# cyclops_r3.net
KiCad netlist of a schematic drawn in EAGLE
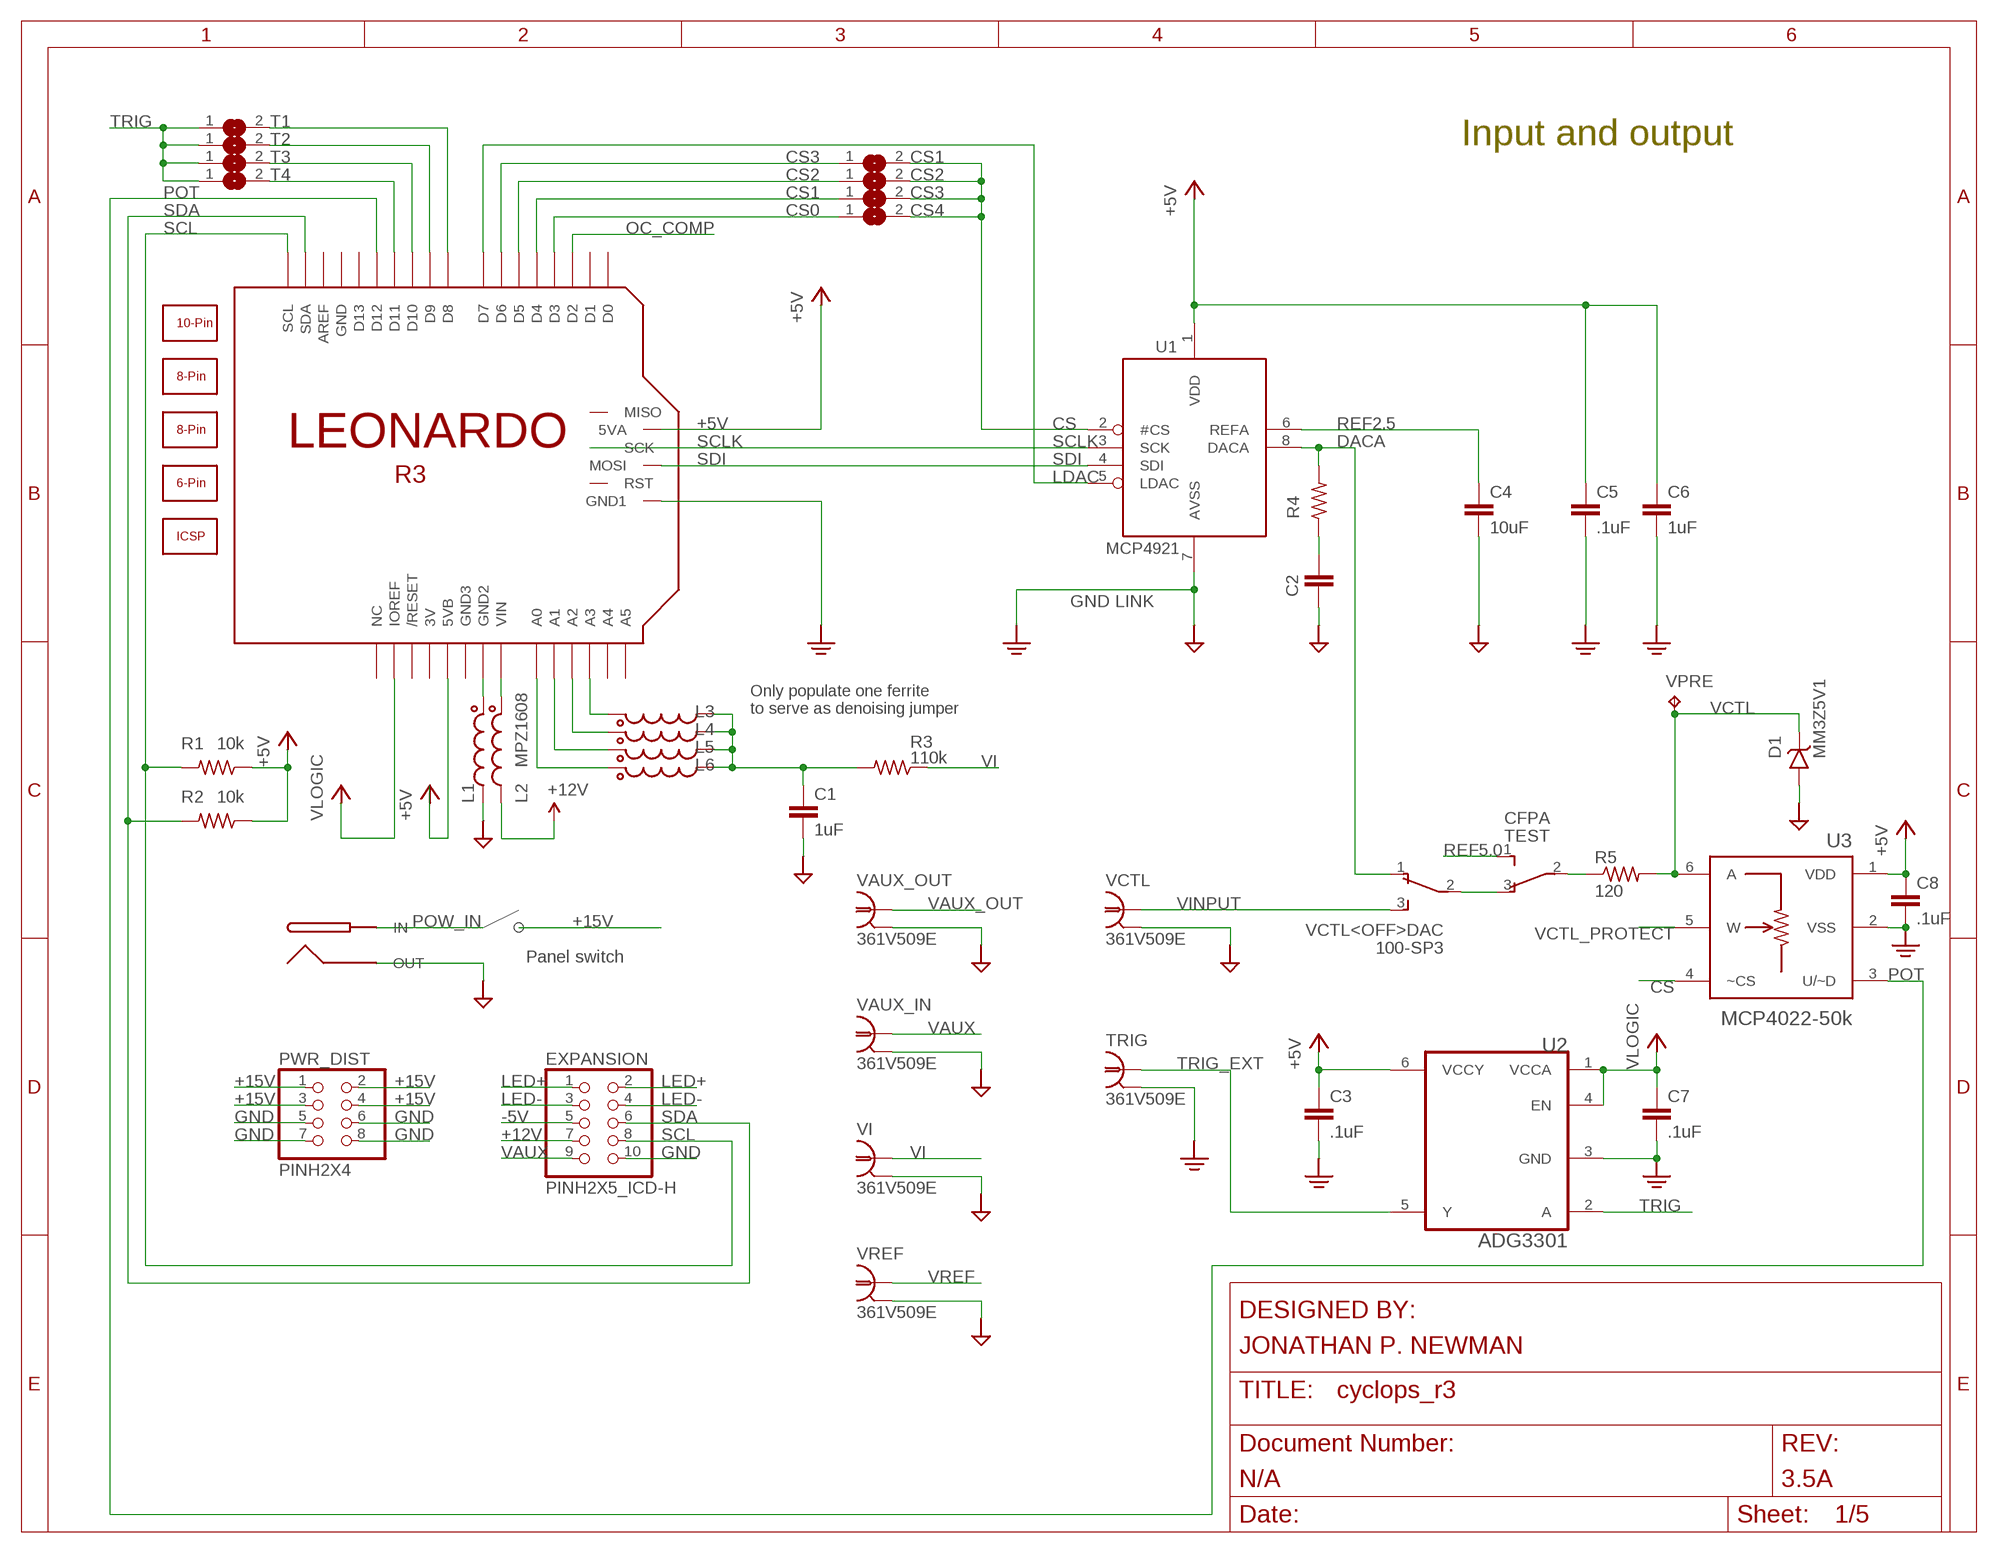
[diagram p0: schematic, sheet 1]
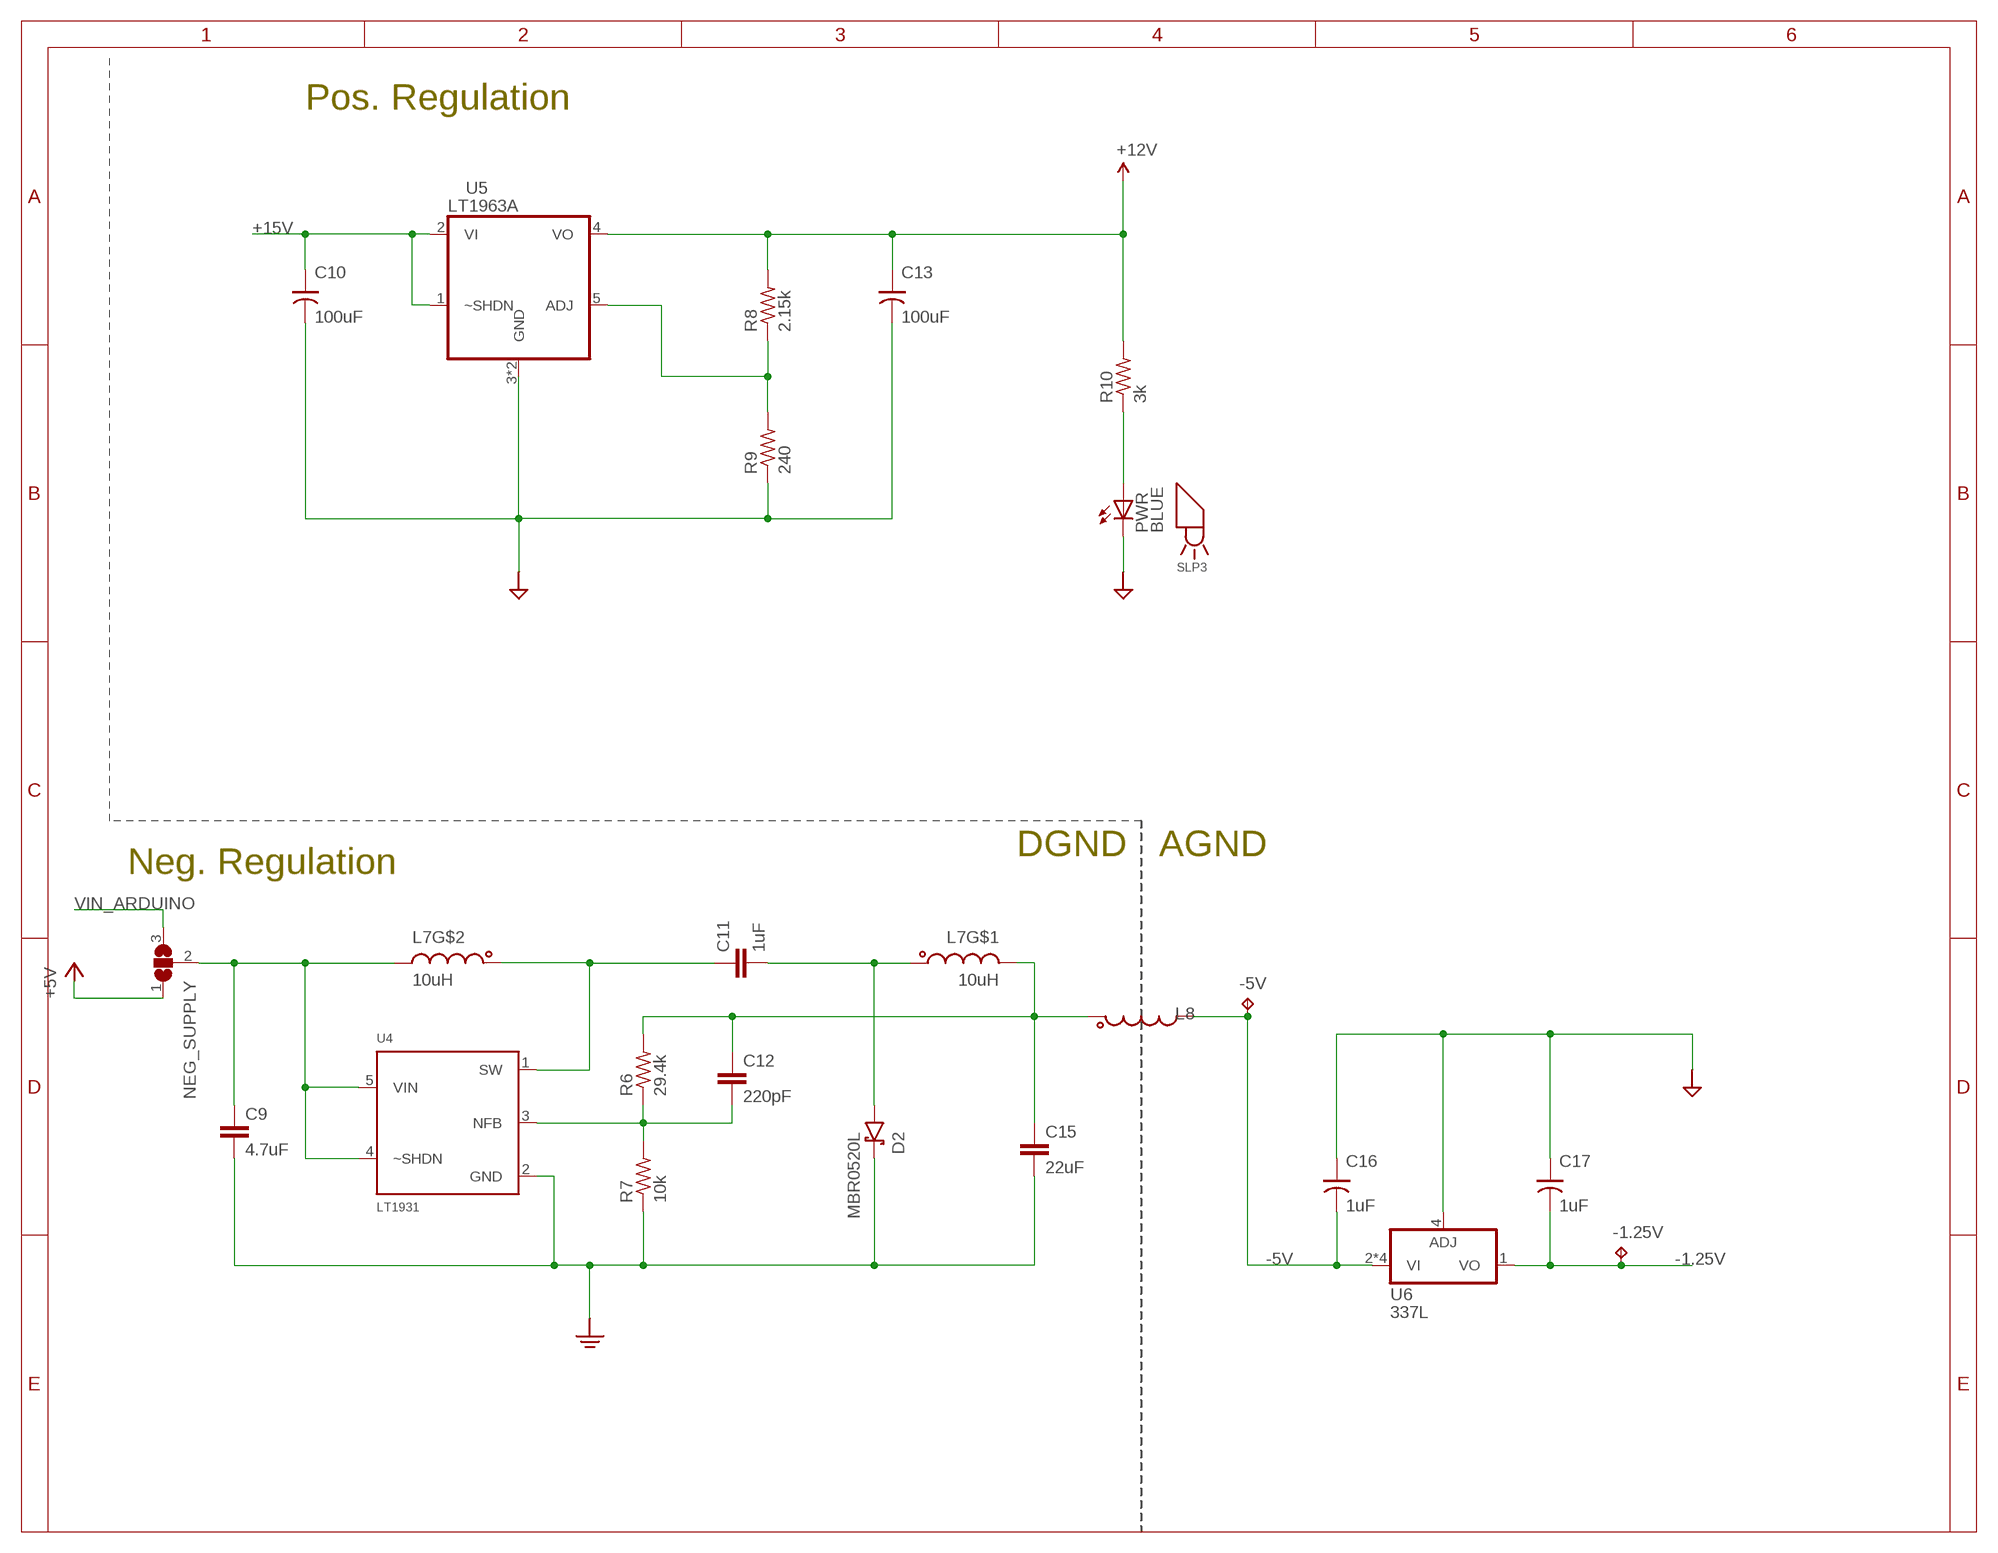
[diagram p1: schematic, sheet 2]
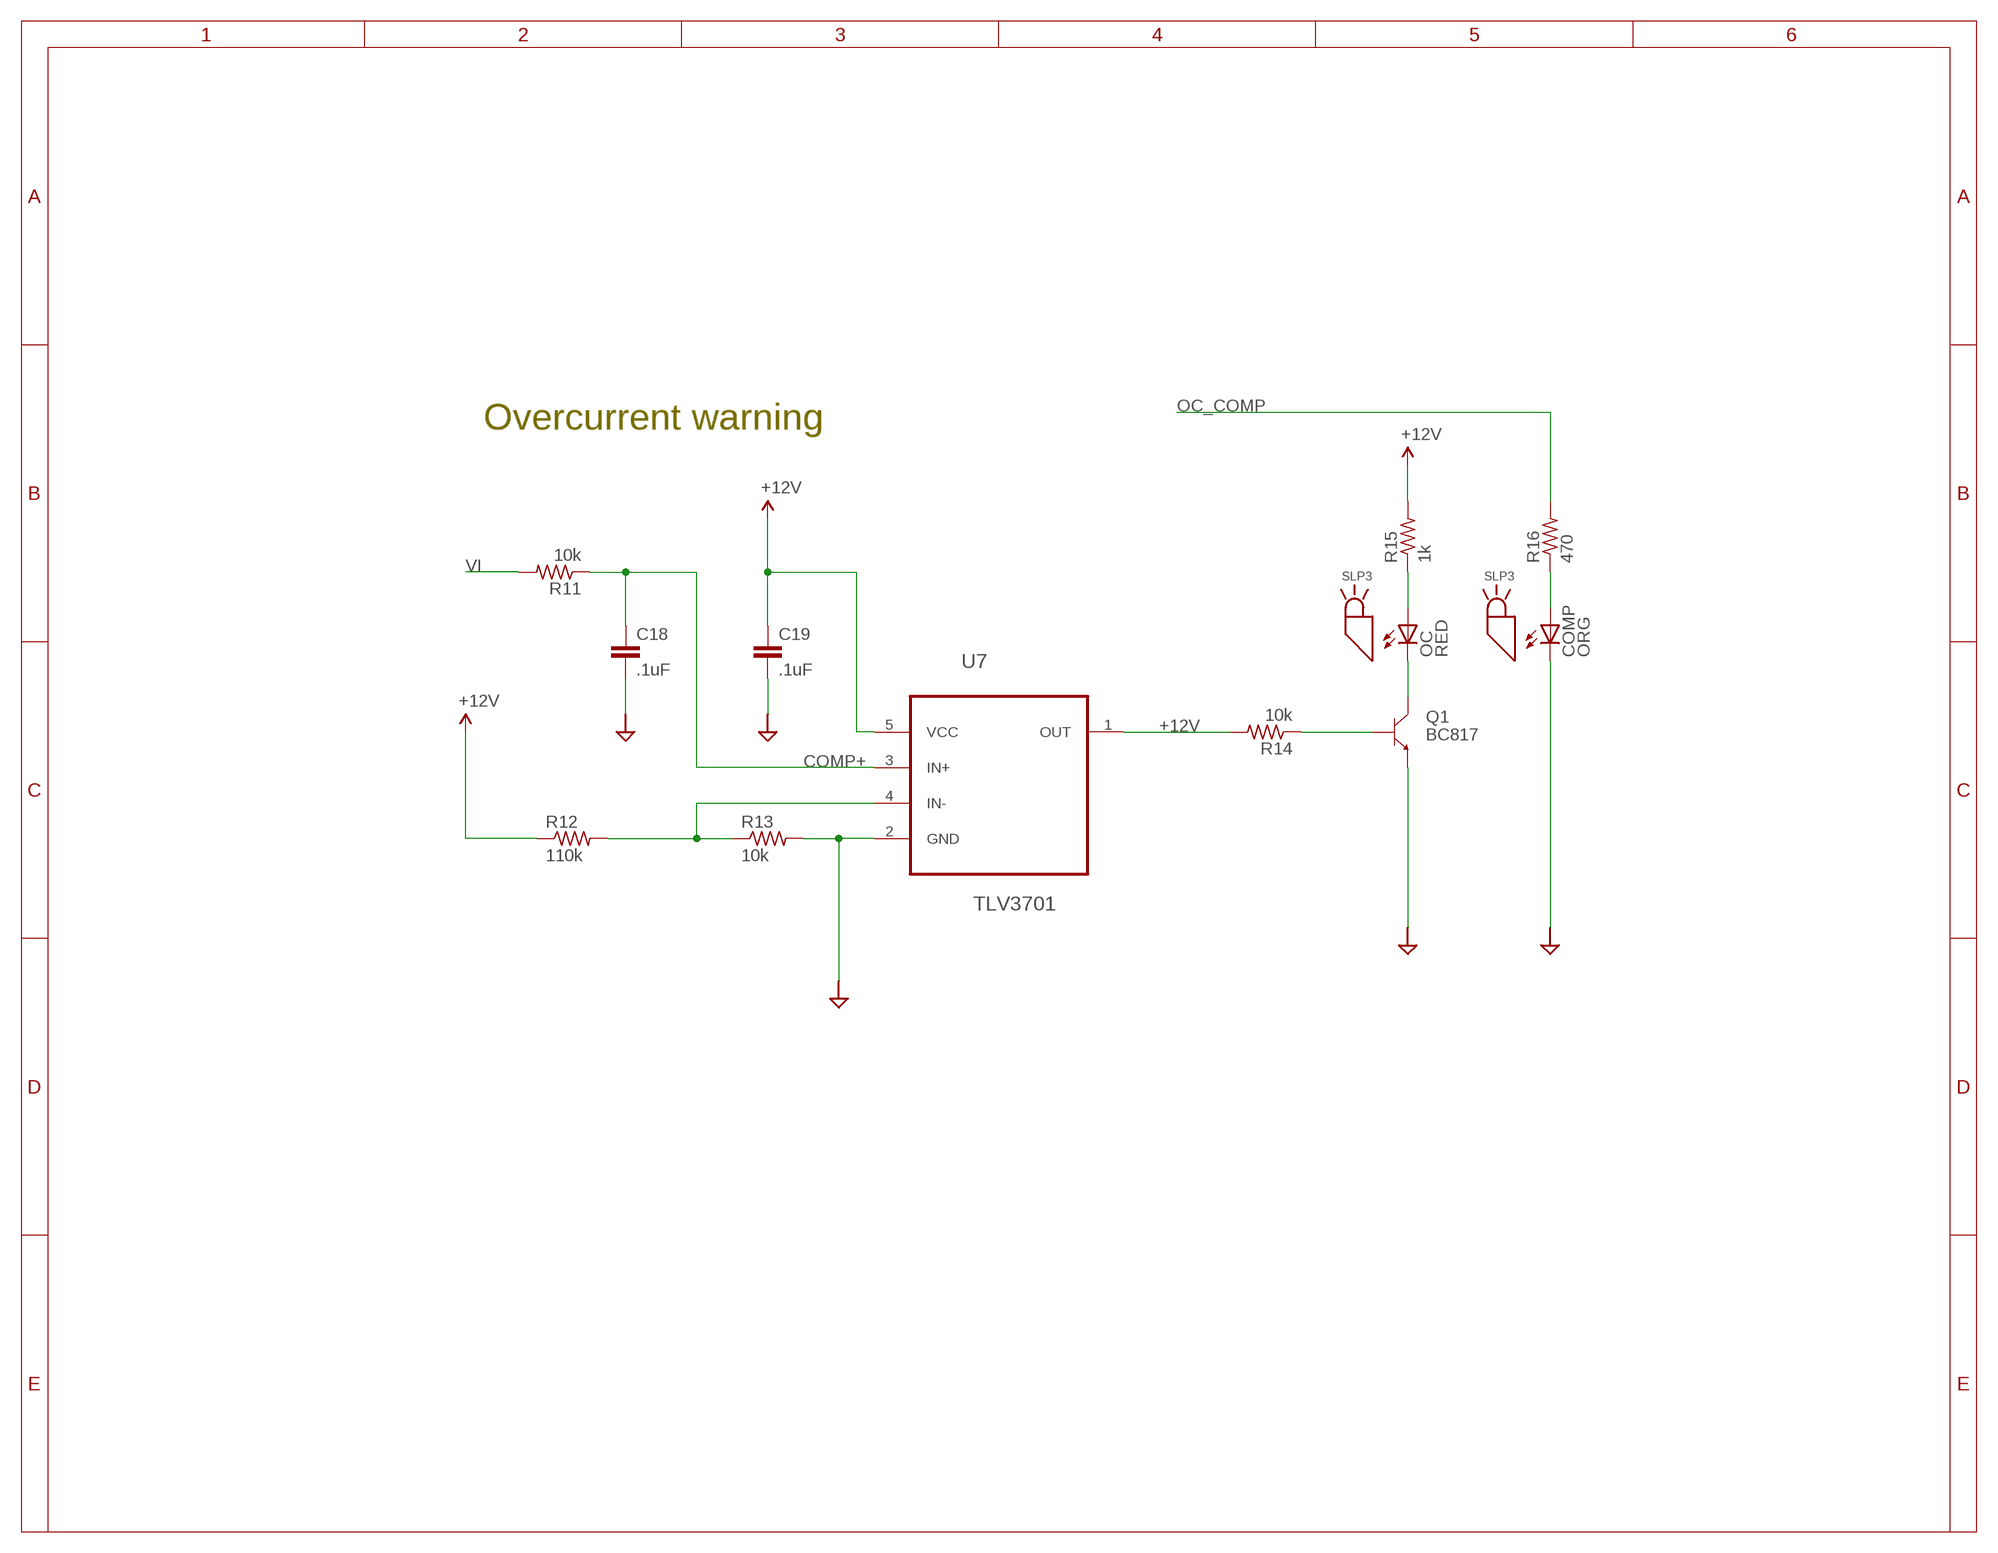
[diagram p2: schematic, sheet 3]
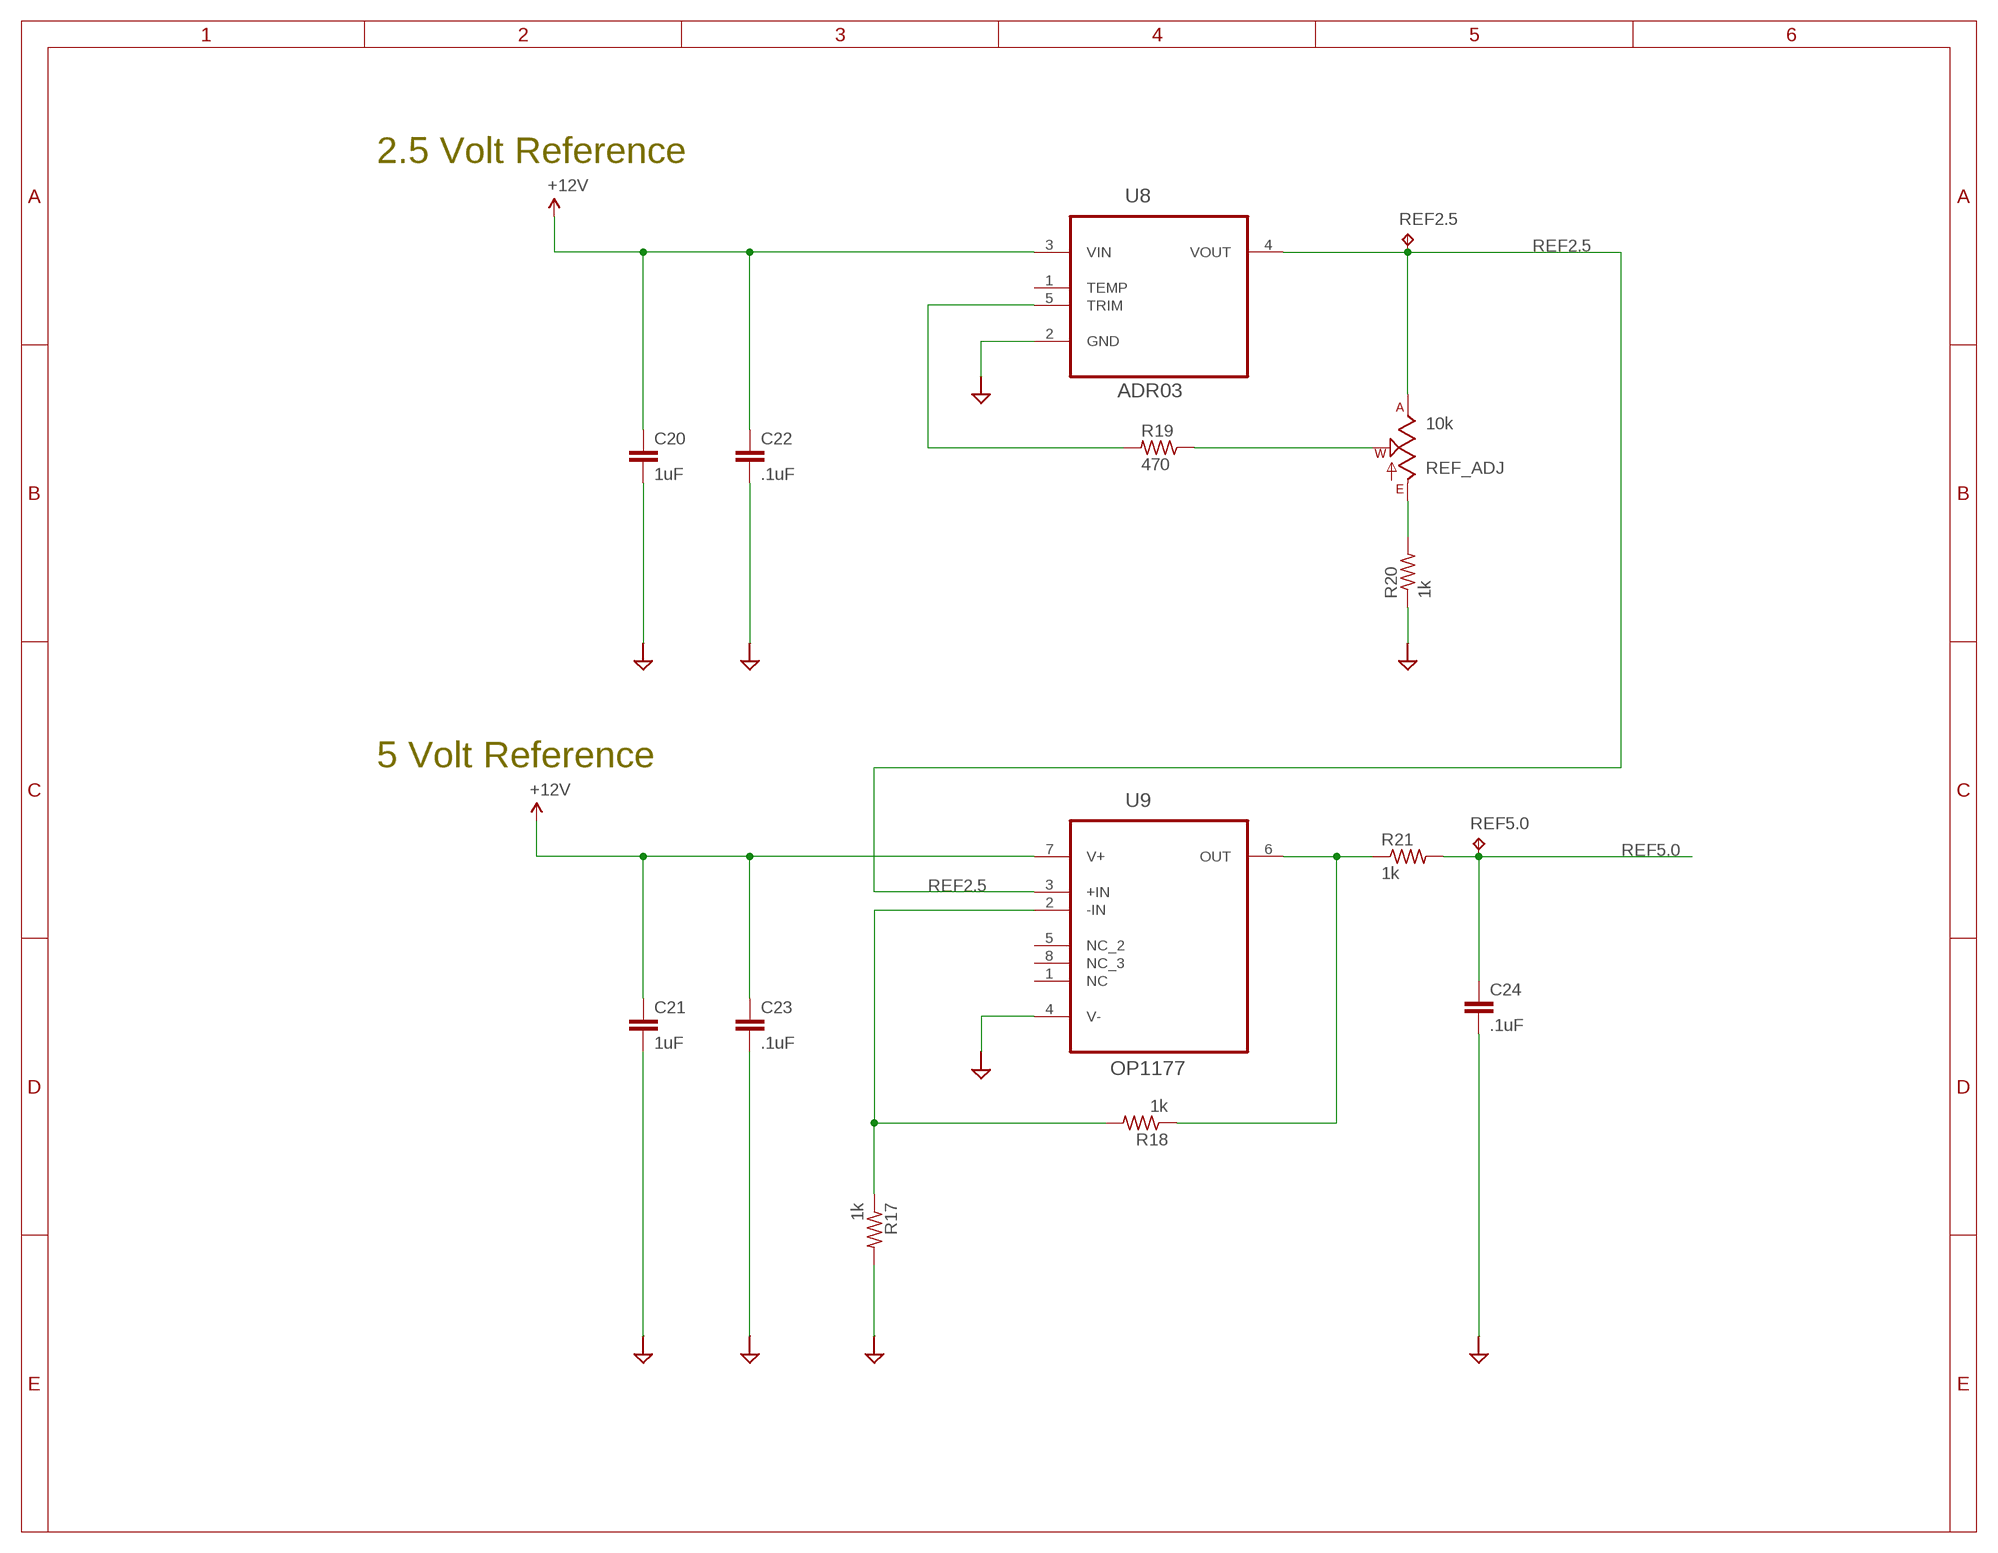
[diagram p3: schematic, sheet 4]
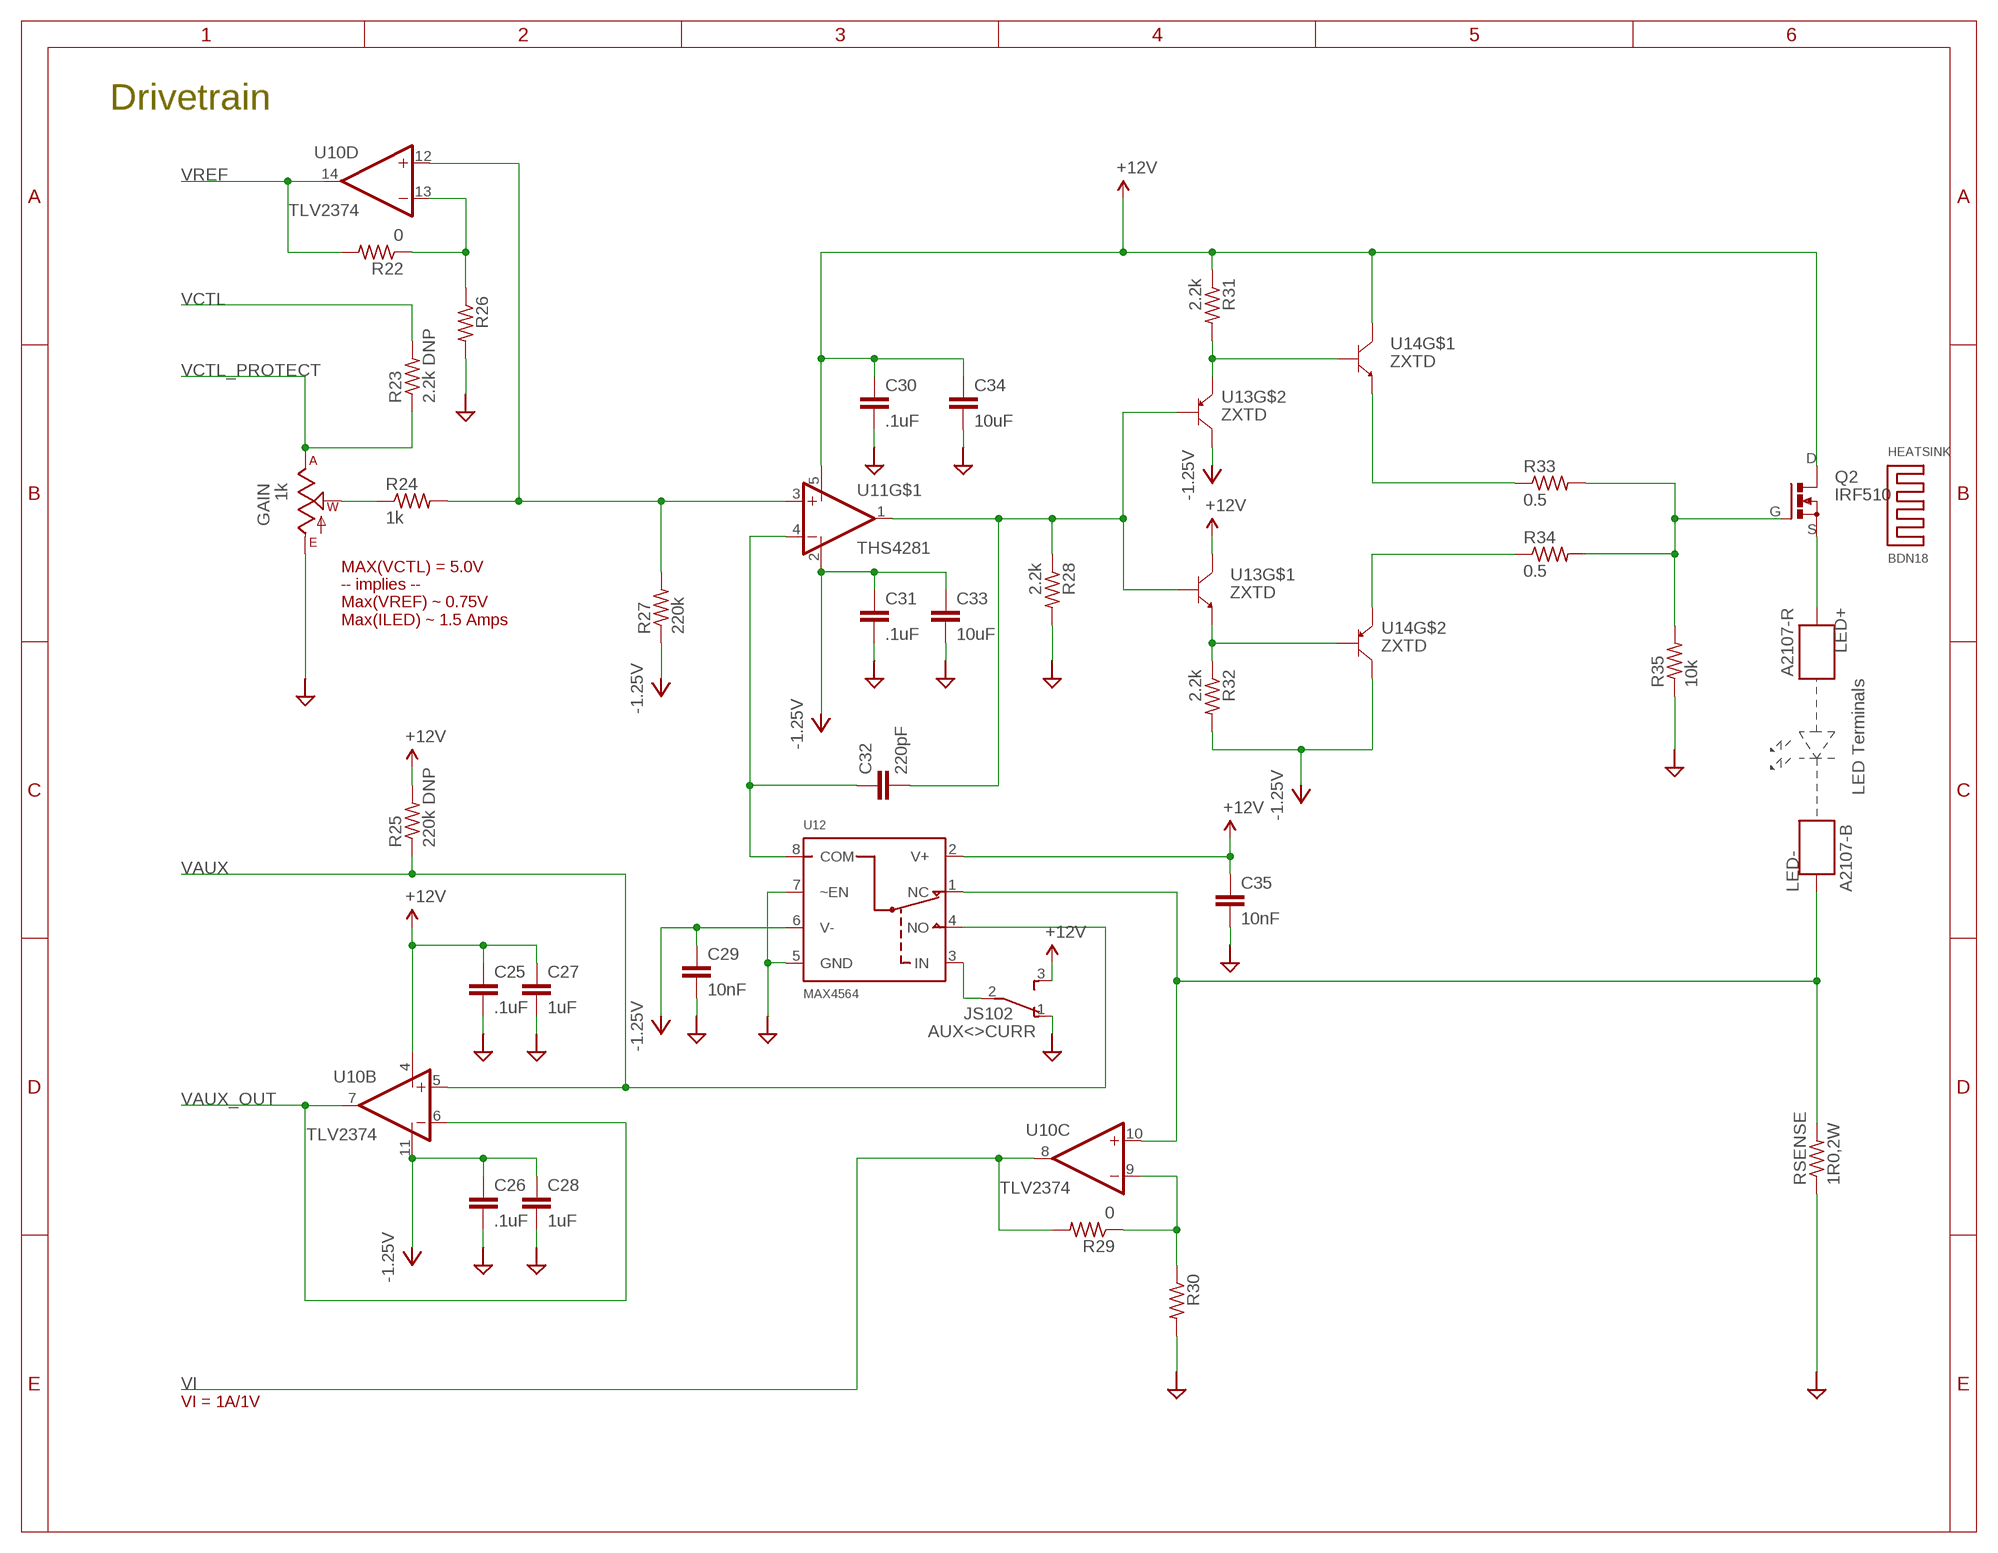
[diagram p4: schematic, sheet 5]

(export (version "E")
  (design (tool "Eeschema 10.0.6"))
  (components
    (comp (ref "C1")
      (value "1uF")
      (footprint "eagle-import:0805")
      (fields (field (name "PARTNO") "C2012X5R1Cxxxxxxx"))
      (libsource (lib "eagle-import") (part "C_0805"))
    )
    (comp (ref "C2")
      (value "C_0603")
      (footprint "eagle-import:0603")
      (libsource (lib "eagle-import") (part "C_0603"))
    )
    (comp (ref "C3")
      (value ".1uF")
      (footprint "eagle-import:0603")
      (libsource (lib "eagle-import") (part "C_0603"))
    )
    (comp (ref "C4")
      (value "10uF")
      (footprint "eagle-import:0805")
      (fields (field (name "PARTNO") "C2012X5R1Cxxxxxxx"))
      (libsource (lib "eagle-import") (part "C_0805"))
    )
    (comp (ref "C5")
      (value ".1uF")
      (footprint "eagle-import:0603")
      (libsource (lib "eagle-import") (part "C_0603"))
    )
    (comp (ref "C6")
      (value "1uF")
      (footprint "eagle-import:0805")
      (fields (field (name "PARTNO") "C2012X5R1Cxxxxxxx"))
      (libsource (lib "eagle-import") (part "C_0805"))
    )
    (comp (ref "C7")
      (value ".1uF")
      (footprint "eagle-import:0603")
      (libsource (lib "eagle-import") (part "C_0603"))
    )
    (comp (ref "C8")
      (value ".1uF")
      (footprint "eagle-import:0603")
      (libsource (lib "eagle-import") (part "C_0603"))
    )
    (comp (ref "CS1") (value "SJ") (footprint "eagle-import:SJ") (libsource (lib "eagle-import") (part "SJ")))
    (comp (ref "CS2") (value "SJ") (footprint "eagle-import:SJ") (libsource (lib "eagle-import") (part "SJ")))
    (comp (ref "CS3") (value "SJ") (footprint "eagle-import:SJ") (libsource (lib "eagle-import") (part "SJ")))
    (comp (ref "CS4") (value "SJ") (footprint "eagle-import:SJ") (libsource (lib "eagle-import") (part "SJ")))
    (comp (ref "D1")
      (value "MM3Z5V1")
      (footprint "eagle-import:SOD-323")
      (libsource (lib "eagle-import") (part "Z-DIODE_SOD-323"))
    )
    (comp (ref "EXPANSION")
      (value "PINH2X5_ICD-H")
      (footprint "eagle-import:2X05-IDC")
      (libsource (lib "eagle-import") (part "PINH2X5_ICD-H"))
    )
    (comp (ref "L1")
      (value "MPZ1608")
      (footprint "eagle-import:0603")
      (libsource (lib "eagle-import") (part "L_0603"))
    )
    (comp (ref "L2")
      (value "MPZ1608")
      (footprint "eagle-import:0603")
      (libsource (lib "eagle-import") (part "L_0603"))
    )
    (comp (ref "L3")
      (value "MPZ1608")
      (footprint "eagle-import:0603")
      (libsource (lib "eagle-import") (part "L_0603"))
    )
    (comp (ref "L4")
      (value "MPZ1608")
      (footprint "eagle-import:0603")
      (libsource (lib "eagle-import") (part "L_0603"))
    )
    (comp (ref "L5")
      (value "MPZ1608")
      (footprint "eagle-import:0603")
      (libsource (lib "eagle-import") (part "L_0603"))
    )
    (comp (ref "L6")
      (value "MPZ1608")
      (footprint "eagle-import:0603")
      (libsource (lib "eagle-import") (part "L_0603"))
    )
    (comp (ref "LEONARDO")
      (value "LEONARDO_R3_ICSP")
      (footprint "eagle-import:ARDUINOR3_PINS_NOHOLES")
      (libsource (lib "eagle-import") (part "LEONARDO_R3_ICSP"))
    )
    (comp (ref "POWER")
      (value "PJ-063BH")
      (footprint "eagle-import:PJ-063BH")
      (libsource (lib "eagle-import") (part "BARREL-JACK_PJ-063BH"))
    )
    (comp (ref "PWR_DIST")
      (value "PINH2X4")
      (footprint "eagle-import:2X04-BIG")
      (libsource (lib "eagle-import") (part "PINH2X4"))
    )
    (comp (ref "R1")
      (value "10k")
      (footprint "eagle-import:0603")
      (fields (field (name "MPN") "ERJ-3EKFxxxxV"))
      (libsource (lib "eagle-import") (part "R_0603"))
    )
    (comp (ref "R2")
      (value "10k")
      (footprint "eagle-import:0603")
      (fields (field (name "MPN") "ERJ-3EKFxxxxV"))
      (libsource (lib "eagle-import") (part "R_0603"))
    )
    (comp (ref "R3")
      (value "110k")
      (footprint "eagle-import:0603")
      (fields (field (name "MPN") "ERJ-3EKFxxxxV"))
      (libsource (lib "eagle-import") (part "R_0603"))
    )
    (comp (ref "R4")
      (value "R_0603")
      (footprint "eagle-import:0603")
      (fields (field (name "MPN") "ERJ-3EKFxxxxV"))
      (libsource (lib "eagle-import") (part "R_0603"))
    )
    (comp (ref "R5")
      (value "120")
      (footprint "eagle-import:0603")
      (fields (field (name "MPN") "ERJ-3EKFxxxxV"))
      (libsource (lib "eagle-import") (part "R_0603"))
    )
    (comp (ref "T1") (value "SJ") (footprint "eagle-import:SJ") (libsource (lib "eagle-import") (part "SJ")))
    (comp (ref "T2") (value "SJ") (footprint "eagle-import:SJ") (libsource (lib "eagle-import") (part "SJ")))
    (comp (ref "T3") (value "SJ") (footprint "eagle-import:SJ") (libsource (lib "eagle-import") (part "SJ")))
    (comp (ref "T4") (value "SJ") (footprint "eagle-import:SJ") (libsource (lib "eagle-import") (part "SJ")))
    (comp (ref "TEST")
      (value "CFPA")
      (footprint "eagle-import:CFPA")
      (libsource (lib "eagle-import") (part "SPDT_CFPA"))
    )
    (comp (ref "TRIG")
      (value "361V509E")
      (footprint "eagle-import:361V509E")
      (libsource (lib "eagle-import") (part "BNC_V-BITE"))
    )
    (comp (ref "U1")
      (value "MCP4921")
      (footprint "eagle-import:SO08")
      (libsource (lib "eagle-import") (part "MCP4921SOIC"))
    )
    (comp (ref "U2")
      (value "ADG3301")
      (footprint "eagle-import:SOT65P210X110-6N")
      (fields (field (name "MPN") "ADG3301BKSZ-REEL"))
      (libsource (lib "eagle-import") (part "ADG3301BKSZ-REEL"))
    )
    (comp (ref "U3")
      (value "MCP4022-50k")
      (footprint "eagle-import:SOT23-6")
      (libsource (lib "eagle-import") (part "MCP4022"))
    )
    (comp (ref "VAUX_IN")
      (value "361V509E")
      (footprint "eagle-import:361V509E")
      (libsource (lib "eagle-import") (part "BNC_V-BITE"))
    )
    (comp (ref "VAUX_OUT")
      (value "361V509E")
      (footprint "eagle-import:361V509E")
      (libsource (lib "eagle-import") (part "BNC_V-BITE"))
    )
    (comp (ref "VCTL")
      (value "361V509E")
      (footprint "eagle-import:361V509E")
      (libsource (lib "eagle-import") (part "BNC_V-BITE"))
    )
    (comp (ref "VCTL<OFF>DAC")
      (value "100-SP3")
      (footprint "eagle-import:2M1-SP1-T2-B4-M6RE")
      (libsource (lib "eagle-import") (part "SPDT_2M-WITHOFF"))
    )
    (comp (ref "VI")
      (value "361V509E")
      (footprint "eagle-import:361V509E")
      (libsource (lib "eagle-import") (part "BNC_V-BITE"))
    )
    (comp (ref "VPRE")
      (value "TPTP16R")
      (footprint "eagle-import:TP16R")
      (libsource (lib "eagle-import") (part "TPTP16R"))
    )
    (comp (ref "VREF")
      (value "361V509E")
      (footprint "eagle-import:361V509E")
      (libsource (lib "eagle-import") (part "BNC_V-BITE"))
    )
    (comp (ref "-1.25V")
      (value "TPTP16R")
      (footprint "eagle-import:TP16R")
      (libsource (lib "eagle-import") (part "TPTP16R"))
    )
    (comp (ref "-5V")
      (value "TPTP16R")
      (footprint "eagle-import:TP16R")
      (libsource (lib "eagle-import") (part "TPTP16R"))
    )
    (comp (ref "C9")
      (value "4.7uF")
      (footprint "eagle-import:1206")
      (libsource (lib "eagle-import") (part "C_1206"))
    )
    (comp (ref "C10")
      (value "100uF")
      (footprint "eagle-import:153CLV-0807")
      (libsource (lib "eagle-import") (part "C-POL_0807"))
    )
    (comp (ref "C11")
      (value "1uF")
      (footprint "eagle-import:1206")
      (libsource (lib "eagle-import") (part "C_1206"))
    )
    (comp (ref "C12")
      (value "220pF")
      (footprint "eagle-import:0603")
      (libsource (lib "eagle-import") (part "C_0603"))
    )
    (comp (ref "C13")
      (value "100uF")
      (footprint "eagle-import:153CLV-0807")
      (libsource (lib "eagle-import") (part "C-POL_0807"))
    )
    (comp (ref "C15")
      (value "22uF")
      (footprint "eagle-import:1210")
      (libsource (lib "eagle-import") (part "C_1210"))
    )
    (comp (ref "C16")
      (value "1uF")
      (footprint "eagle-import:1206-POL")
      (libsource (lib "eagle-import") (part "C-POL_1206"))
    )
    (comp (ref "C17")
      (value "1uF")
      (footprint "eagle-import:1206-POL")
      (libsource (lib "eagle-import") (part "C-POL_1206"))
    )
    (comp (ref "D2")
      (value "MBR0520L")
      (footprint "eagle-import:SOD123")
      (libsource (lib "eagle-import") (part "S-DIODESOD-123"))
    )
    (comp (ref "L7")
      (value "10uH")
      (footprint "eagle-import:CLS62")
      (libsource (lib "eagle-import") (part "2L_CLS62"))
    )
    (comp (ref "L8")
      (value "MPZ1608")
      (footprint "eagle-import:0603")
      (libsource (lib "eagle-import") (part "L_0603"))
    )
    (comp (ref "NEG_SUPPLY")
      (value "SJ2W")
      (footprint "eagle-import:SJ_2")
      (libsource (lib "eagle-import") (part "SJ2W"))
    )
    (comp (ref "PWR")
      (value "BLUE")
      (footprint "eagle-import:LED-0603")
      (libsource (lib "eagle-import") (part "LED_0603"))
    )
    (comp (ref "R6")
      (value "29.4k")
      (footprint "eagle-import:0603")
      (fields (field (name "MPN") "ERJ-3EKFxxxxV"))
      (libsource (lib "eagle-import") (part "R_0603"))
    )
    (comp (ref "R7")
      (value "10k")
      (footprint "eagle-import:0603")
      (fields (field (name "MPN") "ERJ-3EKFxxxxV"))
      (libsource (lib "eagle-import") (part "R_0603"))
    )
    (comp (ref "R8")
      (value "2.15k")
      (footprint "eagle-import:0603")
      (fields (field (name "MPN") "ERJ-3EKFxxxxV"))
      (libsource (lib "eagle-import") (part "R_0603"))
    )
    (comp (ref "R9")
      (value "240")
      (footprint "eagle-import:0603")
      (fields (field (name "MPN") "ERJ-3EKFxxxxV"))
      (libsource (lib "eagle-import") (part "R_0603"))
    )
    (comp (ref "R10")
      (value "3k")
      (footprint "eagle-import:0603")
      (fields (field (name "MPN") "ERJ-3EKFxxxxV"))
      (libsource (lib "eagle-import") (part "R_0603"))
    )
    (comp (ref "U4")
      (value "LT1931")
      (footprint "eagle-import:SOT95P310X175-5N")
      (libsource (lib "eagle-import") (part "LT1611"))
    )
    (comp (ref "U5")
      (value "LT1963A")
      (footprint "eagle-import:5-DDPAK")
      (libsource (lib "eagle-import") (part "LT1963_DDPAK"))
    )
    (comp (ref "U6")
      (value "337L")
      (footprint "eagle-import:SOIC127P600X175-8N")
      (libsource (lib "eagle-import") (part "337L"))
    )
    (comp (ref "X1")
      (value "SLP3")
      (footprint "eagle-import:SL3P-150-100-F")
      (libsource (lib "eagle-import") (part "LIGHT-PIPE_SL30-150-100-F"))
    )
    (comp (ref "C18")
      (value ".1uF")
      (footprint "eagle-import:0603")
      (libsource (lib "eagle-import") (part "C_0603"))
    )
    (comp (ref "C19")
      (value ".1uF")
      (footprint "eagle-import:0603")
      (libsource (lib "eagle-import") (part "C_0603"))
    )
    (comp (ref "COMP")
      (value "ORG")
      (footprint "eagle-import:LED-0603")
      (libsource (lib "eagle-import") (part "LED_0603"))
    )
    (comp (ref "OC")
      (value "RED")
      (footprint "eagle-import:LED-0603")
      (libsource (lib "eagle-import") (part "LED_0603"))
    )
    (comp (ref "Q1")
      (value "BC817")
      (footprint "eagle-import:SOT23-BEC")
      (libsource (lib "eagle-import") (part "BC817SMD-16"))
    )
    (comp (ref "R11")
      (value "10k")
      (footprint "eagle-import:0603")
      (fields (field (name "MPN") "ERJ-3EKFxxxxV"))
      (libsource (lib "eagle-import") (part "R_0603"))
    )
    (comp (ref "R12")
      (value "110k")
      (footprint "eagle-import:0603")
      (fields (field (name "MPN") "ERJ-3EKFxxxxV"))
      (libsource (lib "eagle-import") (part "R_0603"))
    )
    (comp (ref "R13")
      (value "10k")
      (footprint "eagle-import:0603")
      (fields (field (name "MPN") "ERJ-3EKFxxxxV"))
      (libsource (lib "eagle-import") (part "R_0603"))
    )
    (comp (ref "R14")
      (value "10k")
      (footprint "eagle-import:0603")
      (fields (field (name "MPN") "ERJ-3EKFxxxxV"))
      (libsource (lib "eagle-import") (part "R_0603"))
    )
    (comp (ref "R15")
      (value "1k")
      (footprint "eagle-import:0603")
      (fields (field (name "MPN") "ERJ-3EKFxxxxV"))
      (libsource (lib "eagle-import") (part "R_0603"))
    )
    (comp (ref "R16")
      (value "470")
      (footprint "eagle-import:0603")
      (fields (field (name "MPN") "ERJ-3EKFxxxxV"))
      (libsource (lib "eagle-import") (part "R_0603"))
    )
    (comp (ref "U7")
      (value "TLV3701")
      (footprint "eagle-import:SOT95P280X145-5N")
      (fields (field (name "MPN") "TLV3701CDBVT"))
      (libsource (lib "eagle-import") (part "TLV3701CDBVT"))
    )
    (comp (ref "X2")
      (value "SLP3")
      (footprint "eagle-import:SL3P-150-100-F")
      (libsource (lib "eagle-import") (part "LIGHT-PIPE_SL30-150-100-F"))
    )
    (comp (ref "X3")
      (value "SLP3")
      (footprint "eagle-import:SL3P-150-100-F")
      (libsource (lib "eagle-import") (part "LIGHT-PIPE_SL30-150-100-F"))
    )
    (comp (ref "C20")
      (value "1uF")
      (footprint "eagle-import:0805")
      (fields (field (name "PARTNO") "C2012X5R1Cxxxxxxx"))
      (libsource (lib "eagle-import") (part "C_0805"))
    )
    (comp (ref "C21")
      (value "1uF")
      (footprint "eagle-import:0805")
      (fields (field (name "PARTNO") "C2012X5R1Cxxxxxxx"))
      (libsource (lib "eagle-import") (part "C_0805"))
    )
    (comp (ref "C22")
      (value ".1uF")
      (footprint "eagle-import:0603")
      (libsource (lib "eagle-import") (part "C_0603"))
    )
    (comp (ref "C23")
      (value ".1uF")
      (footprint "eagle-import:0603")
      (libsource (lib "eagle-import") (part "C_0603"))
    )
    (comp (ref "C24")
      (value ".1uF")
      (footprint "eagle-import:0603")
      (libsource (lib "eagle-import") (part "C_0603"))
    )
    (comp (ref "R17")
      (value "1k")
      (footprint "eagle-import:0603")
      (fields (field (name "MPN") "ERJ-3EKFxxxxV"))
      (libsource (lib "eagle-import") (part "R_0603"))
    )
    (comp (ref "R18")
      (value "1k")
      (footprint "eagle-import:0603")
      (fields (field (name "MPN") "ERJ-3EKFxxxxV"))
      (libsource (lib "eagle-import") (part "R_0603"))
    )
    (comp (ref "R19")
      (value "470")
      (footprint "eagle-import:0603")
      (fields (field (name "MPN") "ERJ-3EKFxxxxV"))
      (libsource (lib "eagle-import") (part "R_0603"))
    )
    (comp (ref "R20")
      (value "1k")
      (footprint "eagle-import:0603")
      (fields (field (name "MPN") "ERJ-3EKFxxxxV"))
      (libsource (lib "eagle-import") (part "R_0603"))
    )
    (comp (ref "R21")
      (value "1k")
      (footprint "eagle-import:0603")
      (fields (field (name "MPN") "ERJ-3EKFxxxxV"))
      (libsource (lib "eagle-import") (part "R_0603"))
    )
    (comp (ref "REF2.5")
      (value "TPTP16R")
      (footprint "eagle-import:TP16R")
      (libsource (lib "eagle-import") (part "TPTP16R"))
    )
    (comp (ref "REF5.0")
      (value "TPTP16R")
      (footprint "eagle-import:TP16R")
      (libsource (lib "eagle-import") (part "TPTP16R"))
    )
    (comp (ref "REF_ADJ")
      (value "10k")
      (footprint "eagle-import:SM-42_43W")
      (libsource (lib "eagle-import") (part "TRIM_US-SM-42/43W"))
    )
    (comp (ref "U8")
      (value "ADR03")
      (footprint "eagle-import:SOT65P210X110-5N")
      (fields (field (name "MPN") "ADR03AKSZ-REEL7"))
      (libsource (lib "eagle-import") (part "ADR03AKSZ-REEL7"))
    )
    (comp (ref "U9")
      (value "OP1177")
      (footprint "eagle-import:SOP65P490X110-8N")
      (fields (field (name "MPN") "OP1177ARMZ"))
      (libsource (lib "eagle-import") (part "OP1177ARMZ"))
    )
    (comp (ref "AUX<>CURR")
      (value "JS102")
      (footprint "eagle-import:JS102011SAQN")
      (libsource (lib "eagle-import") (part "SPDT_JS"))
    )
    (comp (ref "C25")
      (value ".1uF")
      (footprint "eagle-import:0603")
      (libsource (lib "eagle-import") (part "C_0603"))
    )
    (comp (ref "C26")
      (value ".1uF")
      (footprint "eagle-import:0603")
      (libsource (lib "eagle-import") (part "C_0603"))
    )
    (comp (ref "C27")
      (value "1uF")
      (footprint "eagle-import:0805")
      (fields (field (name "PARTNO") "C2012X5R1Cxxxxxxx"))
      (libsource (lib "eagle-import") (part "C_0805"))
    )
    (comp (ref "C28")
      (value "1uF")
      (footprint "eagle-import:0805")
      (fields (field (name "PARTNO") "C2012X5R1Cxxxxxxx"))
      (libsource (lib "eagle-import") (part "C_0805"))
    )
    (comp (ref "C29")
      (value "10nF")
      (footprint "eagle-import:0603")
      (libsource (lib "eagle-import") (part "C_0603"))
    )
    (comp (ref "C30")
      (value ".1uF")
      (footprint "eagle-import:0603")
      (libsource (lib "eagle-import") (part "C_0603"))
    )
    (comp (ref "C31")
      (value ".1uF")
      (footprint "eagle-import:0603")
      (libsource (lib "eagle-import") (part "C_0603"))
    )
    (comp (ref "C32")
      (value "220pF")
      (footprint "eagle-import:0603")
      (libsource (lib "eagle-import") (part "C_0603"))
    )
    (comp (ref "C33")
      (value "10uF")
      (footprint "eagle-import:1206")
      (libsource (lib "eagle-import") (part "C_1206"))
    )
    (comp (ref "C34")
      (value "10uF")
      (footprint "eagle-import:1206")
      (libsource (lib "eagle-import") (part "C_1206"))
    )
    (comp (ref "C35")
      (value "10nF")
      (footprint "eagle-import:0603")
      (libsource (lib "eagle-import") (part "C_0603"))
    )
    (comp (ref "GAIN")
      (value "1k")
      (footprint "eagle-import:3310C-001")
      (libsource (lib "eagle-import") (part "POT_US_3310"))
    )
    (comp (ref "HEATSINK")
      (value "BDN18")
      (footprint "eagle-import:BDN18")
      (libsource (lib "eagle-import") (part "HEATSINK_BDN18"))
    )
    (comp (ref "LED+")
      (value "A2107-R")
      (footprint "eagle-import:A-2107")
      (libsource (lib "eagle-import") (part "BANANA_TO_BOARD_A2107"))
    )
    (comp (ref "LED-")
      (value "A2107-B")
      (footprint "eagle-import:A-2107")
      (libsource (lib "eagle-import") (part "BANANA_TO_BOARD_A2107"))
    )
    (comp (ref "Q2")
      (value "IRF510")
      (footprint "eagle-import:TO-262_01")
      (libsource (lib "eagle-import") (part "N-MOSFETTO-262"))
    )
    (comp (ref "R22")
      (value "0")
      (footprint "eagle-import:0603")
      (fields (field (name "MPN") "ERJ-3EKFxxxxV"))
      (libsource (lib "eagle-import") (part "R_0603"))
    )
    (comp (ref "R23")
      (value "2.2k")
      (footprint "eagle-import:0603")
      (fields (field (name "MPN") "ERJ-3EKFxxxxV"))
      (libsource (lib "eagle-import") (part "R_0603"))
    )
    (comp (ref "R24")
      (value "1k")
      (footprint "eagle-import:0603")
      (fields (field (name "MPN") "ERJ-3EKFxxxxV"))
      (libsource (lib "eagle-import") (part "R_0603"))
    )
    (comp (ref "R25")
      (value "220k")
      (footprint "eagle-import:0603")
      (fields (field (name "MPN") "ERJ-3EKFxxxxV"))
      (libsource (lib "eagle-import") (part "R_0603"))
    )
    (comp (ref "R26")
      (value "R_0603")
      (footprint "eagle-import:0603")
      (fields (field (name "MPN") "ERJ-3EKFxxxxV"))
      (libsource (lib "eagle-import") (part "R_0603"))
    )
    (comp (ref "R27")
      (value "220k")
      (footprint "eagle-import:0603")
      (fields (field (name "MPN") "ERJ-3EKFxxxxV"))
      (libsource (lib "eagle-import") (part "R_0603"))
    )
    (comp (ref "R28")
      (value "2.2k")
      (footprint "eagle-import:0603")
      (fields (field (name "MPN") "ERJ-3EKFxxxxV"))
      (libsource (lib "eagle-import") (part "R_0603"))
    )
    (comp (ref "R29")
      (value "0")
      (footprint "eagle-import:0603")
      (fields (field (name "MPN") "ERJ-3EKFxxxxV"))
      (libsource (lib "eagle-import") (part "R_0603"))
    )
    (comp (ref "R30")
      (value "R_0603")
      (footprint "eagle-import:0603")
      (fields (field (name "MPN") "ERJ-3EKFxxxxV"))
      (libsource (lib "eagle-import") (part "R_0603"))
    )
    (comp (ref "R31")
      (value "2.2k")
      (footprint "eagle-import:0603")
      (fields (field (name "MPN") "ERJ-3EKFxxxxV"))
      (libsource (lib "eagle-import") (part "R_0603"))
    )
    (comp (ref "R32")
      (value "2.2k")
      (footprint "eagle-import:0603")
      (fields (field (name "MPN") "ERJ-3EKFxxxxV"))
      (libsource (lib "eagle-import") (part "R_0603"))
    )
    (comp (ref "R33")
      (value "0.5")
      (footprint "eagle-import:0603")
      (fields (field (name "MPN") "ERJ-3EKFxxxxV"))
      (libsource (lib "eagle-import") (part "R_0603"))
    )
    (comp (ref "R34")
      (value "0.5")
      (footprint "eagle-import:0603")
      (fields (field (name "MPN") "ERJ-3EKFxxxxV"))
      (libsource (lib "eagle-import") (part "R_0603"))
    )
    (comp (ref "R35")
      (value "10k")
      (footprint "eagle-import:0603")
      (fields (field (name "MPN") "ERJ-3EKFxxxxV"))
      (libsource (lib "eagle-import") (part "R_0603"))
    )
    (comp (ref "RSENSE")
      (value "1R0,2W")
      (footprint "eagle-import:2512")
      (libsource (lib "eagle-import") (part "R_2512"))
    )
    (comp (ref "U10")
      (value "TLV2374")
      (footprint "eagle-import:SO14")
      (libsource (lib "eagle-import") (part "QUAD-OPAMP_14PIND"))
    )
    (comp (ref "U11")
      (value "THS4281")
      (footprint "eagle-import:SOT95P310X175-5N")
      (libsource (lib "eagle-import") (part "OPAMP_SOT-23"))
    )
    (comp (ref "U12")
      (value "MAX4564")
      (footprint "eagle-import:SOT65P300X175-N")
      (libsource (lib "eagle-import") (part "MAX4564"))
    )
    (comp (ref "U13")
      (value "ZXTD")
      (footprint "eagle-import:SOT23-6")
      (libsource (lib "eagle-import") (part "ZXTD4591E6"))
    )
    (comp (ref "U14")
      (value "ZXTD")
      (footprint "eagle-import:SOT23-6")
      (libsource (lib "eagle-import") (part "ZXTD4591E6"))
    )
  )
  (nets
    (net (code "1") (name "+5V") (class "Default")
      (node (ref "C3") (pin "1") (pinfunction "1_1") (pintype "passive"))
      (node (ref "C5") (pin "1") (pinfunction "1_1") (pintype "passive"))
      (node (ref "C6") (pin "1") (pinfunction "1_1") (pintype "passive"))
      (node (ref "C8") (pin "1") (pinfunction "1_1") (pintype "passive"))
      (node (ref "LEONARDO") (pin "5VA") (pinfunction "5VA_5VA") (pintype "passive"))
      (node (ref "LEONARDO") (pin "5VB") (pinfunction "5VB_5VB") (pintype "passive"))
      (node (ref "NEG_SUPPLY") (pin "1") (pinfunction "1_1") (pintype "passive"))
      (node (ref "R1") (pin "1") (pinfunction "1_1") (pintype "passive"))
      (node (ref "R2") (pin "1") (pinfunction "1_1") (pintype "passive"))
      (node (ref "U1") (pin "1") (pinfunction "VDD_1") (pintype "power_in"))
      (node (ref "U2") (pin "6") (pinfunction "VCCY_6") (pintype "power_in"))
      (node (ref "U3") (pin "1") (pinfunction "VDD_1") (pintype "bidirectional"))
    )
    (net (code "2") (name "+12V") (class "Default")
      (node (ref "AUX<>CURR") (pin "3") (pinfunction "3_3") (pintype "passive"))
      (node (ref "C13") (pin "+") (pinfunction "+_+") (pintype "passive"))
      (node (ref "C19") (pin "1") (pinfunction "1_1") (pintype "passive"))
      (node (ref "C20") (pin "1") (pinfunction "1_1") (pintype "passive"))
      (node (ref "C21") (pin "1") (pinfunction "1_1") (pintype "passive"))
      (node (ref "C22") (pin "1") (pinfunction "1_1") (pintype "passive"))
      (node (ref "C23") (pin "1") (pinfunction "1_1") (pintype "passive"))
      (node (ref "C25") (pin "1") (pinfunction "1_1") (pintype "passive"))
      (node (ref "C27") (pin "1") (pinfunction "1_1") (pintype "passive"))
      (node (ref "C30") (pin "1") (pinfunction "1_1") (pintype "passive"))
      (node (ref "C34") (pin "1") (pinfunction "1_1") (pintype "passive"))
      (node (ref "C35") (pin "1") (pinfunction "1_1") (pintype "passive"))
      (node (ref "EXPANSION") (pin "7") (pinfunction "7_7") (pintype "passive"))
      (node (ref "L2") (pin "2") (pinfunction "2_2") (pintype "passive"))
      (node (ref "Q2") (pin "D") (pinfunction "D_D") (pintype "bidirectional"))
      (node (ref "R10") (pin "2") (pinfunction "2_2") (pintype "passive"))
      (node (ref "R12") (pin "1") (pinfunction "1_1") (pintype "passive"))
      (node (ref "R15") (pin "2") (pinfunction "2_2") (pintype "passive"))
      (node (ref "R25") (pin "2") (pinfunction "2_2") (pintype "passive"))
      (node (ref "R31") (pin "1") (pinfunction "1_1") (pintype "passive"))
      (node (ref "R8") (pin "2") (pinfunction "2_2") (pintype "passive"))
      (node (ref "U10") (pin "4") (pinfunction "V+_4") (pintype "power_in"))
      (node (ref "U11") (pin "5") (pinfunction "V+_5") (pintype "power_in"))
      (node (ref "U12") (pin "2") (pinfunction "V+_2") (pintype "bidirectional"))
      (node (ref "U13") (pin "1") (pinfunction "C_1") (pintype "bidirectional"))
      (node (ref "U14") (pin "1") (pinfunction "C_1") (pintype "bidirectional"))
      (node (ref "U5") (pin "4") (pinfunction "VO_4") (pintype "power_in"))
      (node (ref "U7") (pin "5") (pinfunction "VCC_5") (pintype "power_in"))
      (node (ref "U8") (pin "3") (pinfunction "VIN_3") (pintype "power_in"))
      (node (ref "U9") (pin "7") (pinfunction "V+_7") (pintype "power_in"))
    )
    (net (code "3") (name "+15V") (class "Default")
      (node (ref "C10") (pin "+") (pinfunction "+_+") (pintype "passive"))
      (node (ref "PWR_DIST") (pin "1") (pinfunction "1_1") (pintype "passive"))
      (node (ref "PWR_DIST") (pin "2") (pinfunction "2_2") (pintype "passive"))
      (node (ref "PWR_DIST") (pin "3") (pinfunction "3_3") (pintype "passive"))
      (node (ref "PWR_DIST") (pin "4") (pinfunction "4_4") (pintype "passive"))
      (node (ref "U5") (pin "1") (pinfunction "~{SHDN}_1") (pintype "input"))
      (node (ref "U5") (pin "2") (pinfunction "VI_2") (pintype "power_in"))
    )
    (net (code "4") (name "-1.25V") (class "Default")
      (node (ref "-1.25V") (pin "TP") (pinfunction "TP_TP") (pintype "input"))
      (node (ref "C17") (pin "-") (pinfunction "-_-") (pintype "passive"))
      (node (ref "C26") (pin "1") (pinfunction "1_1") (pintype "passive"))
      (node (ref "C28") (pin "1") (pinfunction "1_1") (pintype "passive"))
      (node (ref "C29") (pin "1") (pinfunction "1_1") (pintype "passive"))
      (node (ref "C31") (pin "1") (pinfunction "1_1") (pintype "passive"))
      (node (ref "C33") (pin "1") (pinfunction "1_1") (pintype "passive"))
      (node (ref "R27") (pin "1") (pinfunction "1_1") (pintype "passive"))
      (node (ref "R32") (pin "2") (pinfunction "2_2") (pintype "passive"))
      (node (ref "U10") (pin "11") (pinfunction "V-_11") (pintype "power_in"))
      (node (ref "U11") (pin "2") (pinfunction "V-_2") (pintype "power_in"))
      (node (ref "U12") (pin "6") (pinfunction "V-_6") (pintype "power_in"))
      (node (ref "U13") (pin "3") (pinfunction "C_3") (pintype "bidirectional"))
      (node (ref "U14") (pin "3") (pinfunction "C_3") (pintype "bidirectional"))
      (node (ref "U6") (pin "1") (pinfunction "VO_1") (pintype "passive"))
    )
    (net (code "5") (name "-5V") (class "Default")
      (node (ref "-5V") (pin "TP") (pinfunction "TP_TP") (pintype "input"))
      (node (ref "C16") (pin "-") (pinfunction "-_-") (pintype "passive"))
      (node (ref "EXPANSION") (pin "5") (pinfunction "5_5") (pintype "passive"))
      (node (ref "L8") (pin "2") (pinfunction "2_2") (pintype "passive"))
      (node (ref "U6") (pin "2") (pinfunction "VI_2") (pintype "input"))
      (node (ref "U6") (pin "3") (pinfunction "VI_3") (pintype "input"))
      (node (ref "U6") (pin "6") (pinfunction "VI_6") (pintype "input"))
      (node (ref "U6") (pin "7") (pinfunction "VI_7") (pintype "input"))
    )
    (net (code "6") (name "COMP+") (class "Default")
      (node (ref "C18") (pin "1") (pinfunction "1_1") (pintype "passive"))
      (node (ref "R11") (pin "1") (pinfunction "1_1") (pintype "passive"))
      (node (ref "U7") (pin "3") (pinfunction "IN+_3") (pintype "input"))
    )
    (net (code "7") (name "CS") (class "Default")
      (node (ref "CS1") (pin "2") (pinfunction "2_2") (pintype "passive"))
      (node (ref "CS2") (pin "2") (pinfunction "2_2") (pintype "passive"))
      (node (ref "CS3") (pin "2") (pinfunction "2_2") (pintype "passive"))
      (node (ref "CS4") (pin "2") (pinfunction "2_2") (pintype "passive"))
      (node (ref "U1") (pin "2") (pinfunction "#CS_2") (pintype "input"))
      (node (ref "U3") (pin "4") (pinfunction "~{CS}_4") (pintype "bidirectional"))
    )
    (net (code "8") (name "CS0") (class "Default")
      (node (ref "CS4") (pin "1") (pinfunction "1_1") (pintype "passive"))
      (node (ref "LEONARDO") (pin "D3") (pinfunction "D3_D3") (pintype "bidirectional"))
    )
    (net (code "9") (name "CS1") (class "Default")
      (node (ref "CS3") (pin "1") (pinfunction "1_1") (pintype "passive"))
      (node (ref "LEONARDO") (pin "D4") (pinfunction "D4_D4") (pintype "bidirectional"))
    )
    (net (code "10") (name "CS2") (class "Default")
      (node (ref "CS2") (pin "1") (pinfunction "1_1") (pintype "passive"))
      (node (ref "LEONARDO") (pin "D5") (pinfunction "D5_D5") (pintype "bidirectional"))
    )
    (net (code "11") (name "CS3") (class "Default")
      (node (ref "CS1") (pin "1") (pinfunction "1_1") (pintype "passive"))
      (node (ref "LEONARDO") (pin "D6") (pinfunction "D6_D6") (pintype "bidirectional"))
    )
    (net (code "12") (name "DACA") (class "Default")
      (node (ref "R4") (pin "2") (pinfunction "2_2") (pintype "passive"))
      (node (ref "U1") (pin "8") (pinfunction "DACA_8") (pintype "output"))
      (node (ref "VCTL<OFF>DAC") (pin "1") (pinfunction "1_1") (pintype "passive"))
    )
    (net (code "13") (name "GND") (class "Default")
      (node (ref "AUX<>CURR") (pin "1") (pinfunction "1_1") (pintype "passive"))
      (node (ref "C1") (pin "2") (pinfunction "2_2") (pintype "passive"))
      (node (ref "C10") (pin "-") (pinfunction "-_-") (pintype "passive"))
      (node (ref "C13") (pin "-") (pinfunction "-_-") (pintype "passive"))
      (node (ref "C15") (pin "2") (pinfunction "2_2") (pintype "passive"))
      (node (ref "C16") (pin "+") (pinfunction "+_+") (pintype "passive"))
      (node (ref "C17") (pin "+") (pinfunction "+_+") (pintype "passive"))
      (node (ref "C18") (pin "2") (pinfunction "2_2") (pintype "passive"))
      (node (ref "C19") (pin "2") (pinfunction "2_2") (pintype "passive"))
      (node (ref "C2") (pin "2") (pinfunction "2_2") (pintype "passive"))
      (node (ref "C20") (pin "2") (pinfunction "2_2") (pintype "passive"))
      (node (ref "C21") (pin "2") (pinfunction "2_2") (pintype "passive"))
      (node (ref "C22") (pin "2") (pinfunction "2_2") (pintype "passive"))
      (node (ref "C23") (pin "2") (pinfunction "2_2") (pintype "passive"))
      (node (ref "C24") (pin "2") (pinfunction "2_2") (pintype "passive"))
      (node (ref "C25") (pin "2") (pinfunction "2_2") (pintype "passive"))
      (node (ref "C26") (pin "2") (pinfunction "2_2") (pintype "passive"))
      (node (ref "C27") (pin "2") (pinfunction "2_2") (pintype "passive"))
      (node (ref "C28") (pin "2") (pinfunction "2_2") (pintype "passive"))
      (node (ref "C29") (pin "2") (pinfunction "2_2") (pintype "passive"))
      (node (ref "C3") (pin "2") (pinfunction "2_2") (pintype "passive"))
      (node (ref "C30") (pin "2") (pinfunction "2_2") (pintype "passive"))
      (node (ref "C31") (pin "2") (pinfunction "2_2") (pintype "passive"))
      (node (ref "C33") (pin "2") (pinfunction "2_2") (pintype "passive"))
      (node (ref "C34") (pin "2") (pinfunction "2_2") (pintype "passive"))
      (node (ref "C35") (pin "2") (pinfunction "2_2") (pintype "passive"))
      (node (ref "C4") (pin "2") (pinfunction "2_2") (pintype "passive"))
      (node (ref "C5") (pin "2") (pinfunction "2_2") (pintype "passive"))
      (node (ref "C6") (pin "2") (pinfunction "2_2") (pintype "passive"))
      (node (ref "C7") (pin "2") (pinfunction "2_2") (pintype "passive"))
      (node (ref "C8") (pin "2") (pinfunction "2_2") (pintype "passive"))
      (node (ref "C9") (pin "2") (pinfunction "2_2") (pintype "passive"))
      (node (ref "COMP") (pin "C") (pinfunction "C_C") (pintype "passive"))
      (node (ref "D1") (pin "A") (pinfunction "A_A") (pintype "passive"))
      (node (ref "D2") (pin "C") (pinfunction "C_C") (pintype "passive"))
      (node (ref "EXPANSION") (pin "10") (pinfunction "10_10") (pintype "passive"))
      (node (ref "GAIN") (pin "1") (pinfunction "E_1") (pintype "passive"))
      (node (ref "L1") (pin "2") (pinfunction "2_2") (pintype "passive"))
      (node (ref "LEONARDO") (pin "GND1") (pinfunction "GND1_GND1") (pintype "passive"))
      (node (ref "POWER") (pin "2") (pinfunction "OUT_2") (pintype "bidirectional"))
      (node (ref "PWR") (pin "C") (pinfunction "C_C") (pintype "passive"))
      (node (ref "PWR_DIST") (pin "5") (pinfunction "5_5") (pintype "passive"))
      (node (ref "PWR_DIST") (pin "6") (pinfunction "6_6") (pintype "passive"))
      (node (ref "PWR_DIST") (pin "7") (pinfunction "7_7") (pintype "passive"))
      (node (ref "PWR_DIST") (pin "8") (pinfunction "8_8") (pintype "passive"))
      (node (ref "Q1") (pin "E") (pinfunction "E_E") (pintype "bidirectional"))
      (node (ref "R13") (pin "2") (pinfunction "2_2") (pintype "passive"))
      (node (ref "R17") (pin "2") (pinfunction "2_2") (pintype "passive"))
      (node (ref "R20") (pin "1") (pinfunction "1_1") (pintype "passive"))
      (node (ref "R26") (pin "2") (pinfunction "2_2") (pintype "passive"))
      (node (ref "R28") (pin "2") (pinfunction "2_2") (pintype "passive"))
      (node (ref "R30") (pin "2") (pinfunction "2_2") (pintype "passive"))
      (node (ref "R35") (pin "1") (pinfunction "1_1") (pintype "passive"))
      (node (ref "R7") (pin "1") (pinfunction "1_1") (pintype "passive"))
      (node (ref "R9") (pin "1") (pinfunction "1_1") (pintype "passive"))
      (node (ref "RSENSE") (pin "1") (pinfunction "1_1") (pintype "passive"))
      (node (ref "TRIG") (pin "2") (pinfunction "2_2") (pintype "passive"))
      (node (ref "TRIG") (pin "3") (pinfunction "2_3") (pintype "passive"))
      (node (ref "U1") (pin "7") (pinfunction "AVSS_7") (pintype "power_in"))
      (node (ref "U12") (pin "5") (pinfunction "GND_5") (pintype "power_in"))
      (node (ref "U12") (pin "7") (pinfunction "~{EN}_7") (pintype "bidirectional"))
      (node (ref "U2") (pin "3") (pinfunction "GND_3") (pintype "passive"))
      (node (ref "U3") (pin "2") (pinfunction "VSS_2") (pintype "bidirectional"))
      (node (ref "U4") (pin "2") (pinfunction "GND_2") (pintype "power_in"))
      (node (ref "U5") (pin "3") (pinfunction "GND_3") (pintype "power_in"))
      (node (ref "U5") (pin "TAB") (pinfunction "GND_TAB") (pintype "power_in"))
      (node (ref "U6") (pin "4") (pinfunction "ADJ_4") (pintype "input"))
      (node (ref "U7") (pin "2") (pinfunction "GND_2") (pintype "passive"))
      (node (ref "U8") (pin "2") (pinfunction "GND_2") (pintype "passive"))
      (node (ref "U9") (pin "4") (pinfunction "V-_4") (pintype "power_in"))
      (node (ref "VAUX_IN") (pin "2") (pinfunction "2_2") (pintype "passive"))
      (node (ref "VAUX_IN") (pin "3") (pinfunction "2_3") (pintype "passive"))
      (node (ref "VAUX_OUT") (pin "2") (pinfunction "2_2") (pintype "passive"))
      (node (ref "VAUX_OUT") (pin "3") (pinfunction "2_3") (pintype "passive"))
      (node (ref "VCTL") (pin "2") (pinfunction "2_2") (pintype "passive"))
      (node (ref "VCTL") (pin "3") (pinfunction "2_3") (pintype "passive"))
      (node (ref "VI") (pin "2") (pinfunction "2_2") (pintype "passive"))
      (node (ref "VI") (pin "3") (pinfunction "2_3") (pintype "passive"))
      (node (ref "VREF") (pin "2") (pinfunction "2_2") (pintype "passive"))
      (node (ref "VREF") (pin "3") (pinfunction "2_3") (pintype "passive"))
    )
    (net (code "14") (name "LDAC") (class "Default")
      (node (ref "LEONARDO") (pin "D7") (pinfunction "D7_D7") (pintype "bidirectional"))
      (node (ref "U1") (pin "5") (pinfunction "LDAC_5") (pintype "input"))
    )
    (net (code "15") (name "LED+") (class "Default")
      (node (ref "EXPANSION") (pin "1") (pinfunction "1_1") (pintype "passive"))
      (node (ref "EXPANSION") (pin "2") (pinfunction "2_2") (pintype "passive"))
      (node (ref "LED+") (pin "1") (pinfunction "1_1") (pintype "bidirectional"))
      (node (ref "LED+") (pin "2") (pinfunction "1_2") (pintype "bidirectional"))
      (node (ref "Q2") (pin "S") (pinfunction "S_S") (pintype "bidirectional"))
    )
    (net (code "16") (name "LED-") (class "Default")
      (node (ref "EXPANSION") (pin "3") (pinfunction "3_3") (pintype "passive"))
      (node (ref "EXPANSION") (pin "4") (pinfunction "4_4") (pintype "passive"))
      (node (ref "LED-") (pin "1") (pinfunction "1_1") (pintype "bidirectional"))
      (node (ref "LED-") (pin "2") (pinfunction "1_2") (pintype "bidirectional"))
      (node (ref "RSENSE") (pin "2") (pinfunction "2_2") (pintype "passive"))
      (node (ref "U10") (pin "10") (pinfunction "+IN_10") (pintype "input"))
      (node (ref "U12") (pin "1") (pinfunction "NC_1") (pintype "bidirectional"))
    )
    (net (code "17") (name "Net-(C1-Pad1)") (class "Default")
      (node (ref "C1") (pin "1") (pinfunction "1_1") (pintype "passive"))
      (node (ref "L3") (pin "2") (pinfunction "2_2") (pintype "passive"))
      (node (ref "L4") (pin "2") (pinfunction "2_2") (pintype "passive"))
      (node (ref "L5") (pin "2") (pinfunction "2_2") (pintype "passive"))
      (node (ref "L6") (pin "2") (pinfunction "2_2") (pintype "passive"))
      (node (ref "R3") (pin "2") (pinfunction "2_2") (pintype "passive"))
    )
    (net (code "18") (name "Net-(C2-Pad1)") (class "Default")
      (node (ref "C2") (pin "1") (pinfunction "1_1") (pintype "passive"))
      (node (ref "R4") (pin "1") (pinfunction "1_1") (pintype "passive"))
    )
    (net (code "19") (name "Net-(C11-Pad2)") (class "Default")
      (node (ref "C11") (pin "2") (pinfunction "2_2") (pintype "passive"))
      (node (ref "D2") (pin "A") (pinfunction "A_A") (pintype "passive"))
      (node (ref "L7") (pin "1") (pinfunction "1_1") (pintype "passive"))
    )
    (net (code "20") (name "Net-(COMP-PadA)") (class "Default")
      (node (ref "COMP") (pin "A") (pinfunction "A_A") (pintype "passive"))
      (node (ref "R16") (pin "1") (pinfunction "1_1") (pintype "passive"))
    )
    (net (code "21") (name "Net-(GAIN-W)") (class "Default")
      (node (ref "GAIN") (pin "2") (pinfunction "W_2") (pintype "passive"))
      (node (ref "R24") (pin "1") (pinfunction "1_1") (pintype "passive"))
    )
    (net (code "22") (name "Net-(L1-Pad1)") (class "Default")
      (node (ref "L1") (pin "1") (pinfunction "1_1") (pintype "passive"))
      (node (ref "LEONARDO") (pin "GND2") (pinfunction "GND2_GND2") (pintype "passive"))
    )
    (net (code "23") (name "Net-(L3-Pad1)") (class "Default")
      (node (ref "L3") (pin "1") (pinfunction "1_1") (pintype "passive"))
      (node (ref "LEONARDO") (pin "A3") (pinfunction "A3_A3") (pintype "bidirectional"))
    )
    (net (code "24") (name "Net-(L4-Pad1)") (class "Default")
      (node (ref "L4") (pin "1") (pinfunction "1_1") (pintype "passive"))
      (node (ref "LEONARDO") (pin "A2") (pinfunction "A2_A2") (pintype "bidirectional"))
    )
    (net (code "25") (name "Net-(L5-Pad1)") (class "Default")
      (node (ref "L5") (pin "1") (pinfunction "1_1") (pintype "passive"))
      (node (ref "LEONARDO") (pin "A1") (pinfunction "A1_A1") (pintype "bidirectional"))
    )
    (net (code "26") (name "Net-(L6-Pad1)") (class "Default")
      (node (ref "L6") (pin "1") (pinfunction "1_1") (pintype "passive"))
      (node (ref "LEONARDO") (pin "A0") (pinfunction "A0_A0") (pintype "bidirectional"))
    )
    (net (code "27") (name "Net-(L7A-2)") (class "Default")
      (node (ref "C12") (pin "1") (pinfunction "1_1") (pintype "passive"))
      (node (ref "C15") (pin "1") (pinfunction "1_1") (pintype "passive"))
      (node (ref "L7") (pin "4") (pinfunction "2_4") (pintype "passive"))
      (node (ref "L8") (pin "1") (pinfunction "1_1") (pintype "passive"))
      (node (ref "R6") (pin "2") (pinfunction "2_2") (pintype "passive"))
    )
    (net (code "28") (name "Net-(L7B-1)") (class "Default")
      (node (ref "C11") (pin "1") (pinfunction "1_1") (pintype "passive"))
      (node (ref "L7") (pin "2") (pinfunction "1_2") (pintype "passive"))
      (node (ref "U4") (pin "1") (pinfunction "SW_1") (pintype "bidirectional"))
    )
    (net (code "29") (name "Net-(L7B-2)") (class "Default")
      (node (ref "C9") (pin "1") (pinfunction "1_1") (pintype "passive"))
      (node (ref "L7") (pin "3") (pinfunction "2_3") (pintype "passive"))
      (node (ref "NEG_SUPPLY") (pin "2") (pinfunction "2_2") (pintype "passive"))
      (node (ref "U4") (pin "4") (pinfunction "~{SHDN}_4") (pintype "bidirectional"))
      (node (ref "U4") (pin "5") (pinfunction "VIN_5") (pintype "power_in"))
    )
    (net (code "30") (name "Net-(LEONARDO-PadD8)") (class "Default")
      (node (ref "LEONARDO") (pin "D8") (pinfunction "D8_D8") (pintype "bidirectional"))
      (node (ref "T1") (pin "2") (pinfunction "2_2") (pintype "passive"))
    )
    (net (code "31") (name "Net-(LEONARDO-PadD9)") (class "Default")
      (node (ref "LEONARDO") (pin "D9") (pinfunction "D9_D9") (pintype "bidirectional"))
      (node (ref "T2") (pin "2") (pinfunction "2_2") (pintype "passive"))
    )
    (net (code "32") (name "Net-(LEONARDO-PadD10)") (class "Default")
      (node (ref "LEONARDO") (pin "D10") (pinfunction "D10_D10") (pintype "bidirectional"))
      (node (ref "T3") (pin "2") (pinfunction "2_2") (pintype "passive"))
    )
    (net (code "33") (name "Net-(LEONARDO-PadD11)") (class "Default")
      (node (ref "LEONARDO") (pin "D11") (pinfunction "D11_D11") (pintype "bidirectional"))
      (node (ref "T4") (pin "2") (pinfunction "2_2") (pintype "passive"))
    )
    (net (code "34") (name "Net-(OC-PadA)") (class "Default")
      (node (ref "OC") (pin "A") (pinfunction "A_A") (pintype "passive"))
      (node (ref "R15") (pin "1") (pinfunction "1_1") (pintype "passive"))
    )
    (net (code "35") (name "Net-(OC-PadC)") (class "Default")
      (node (ref "OC") (pin "C") (pinfunction "C_C") (pintype "passive"))
      (node (ref "Q1") (pin "C") (pinfunction "C_C") (pintype "bidirectional"))
    )
    (net (code "36") (name "Net-(PWR-PadA)") (class "Default")
      (node (ref "PWR") (pin "A") (pinfunction "A_A") (pintype "passive"))
      (node (ref "R10") (pin "1") (pinfunction "1_1") (pintype "passive"))
    )
    (net (code "37") (name "Net-(Q1-PadB)") (class "Default")
      (node (ref "Q1") (pin "B") (pinfunction "B_B") (pintype "input"))
      (node (ref "R14") (pin "1") (pinfunction "1_1") (pintype "passive"))
    )
    (net (code "38") (name "Net-(Q2-PadG)") (class "Default")
      (node (ref "Q2") (pin "G") (pinfunction "G_G") (pintype "bidirectional"))
      (node (ref "R33") (pin "2") (pinfunction "2_2") (pintype "passive"))
      (node (ref "R34") (pin "2") (pinfunction "2_2") (pintype "passive"))
      (node (ref "R35") (pin "2") (pinfunction "2_2") (pintype "passive"))
    )
    (net (code "39") (name "Net-(R5-Pad1)") (class "Default")
      (node (ref "R5") (pin "1") (pinfunction "1_1") (pintype "passive"))
      (node (ref "TEST") (pin "2") (pinfunction "2_2") (pintype "passive"))
    )
    (net (code "40") (name "Net-(REF_ADJ-E)") (class "Default")
      (node (ref "R20") (pin "2") (pinfunction "2_2") (pintype "passive"))
      (node (ref "REF_ADJ") (pin "3") (pinfunction "E_3") (pintype "passive"))
    )
    (net (code "41") (name "Net-(REF_ADJ-W)") (class "Default")
      (node (ref "R19") (pin "1") (pinfunction "1_1") (pintype "passive"))
      (node (ref "REF_ADJ") (pin "2") (pinfunction "W_2") (pintype "passive"))
    )
    (net (code "42") (name "Net-(TEST-1)") (class "Default")
      (node (ref "TEST") (pin "3") (pinfunction "1_3") (pintype "passive"))
      (node (ref "VCTL<OFF>DAC") (pin "2") (pinfunction "2_2") (pintype "passive"))
    )
    (net (code "43") (name "Net-(U4-NFB)") (class "Default")
      (node (ref "C12") (pin "2") (pinfunction "2_2") (pintype "passive"))
      (node (ref "R6") (pin "1") (pinfunction "1_1") (pintype "passive"))
      (node (ref "R7") (pin "2") (pinfunction "2_2") (pintype "passive"))
      (node (ref "U4") (pin "3") (pinfunction "NFB_3") (pintype "bidirectional"))
    )
    (net (code "44") (name "Net-(U5-ADJ)") (class "Default")
      (node (ref "R8") (pin "1") (pinfunction "1_1") (pintype "passive"))
      (node (ref "R9") (pin "2") (pinfunction "2_2") (pintype "passive"))
      (node (ref "U5") (pin "5") (pinfunction "ADJ_5") (pintype "input"))
    )
    (net (code "45") (name "Net-(U7-IN-)") (class "Default")
      (node (ref "R12") (pin "2") (pinfunction "2_2") (pintype "passive"))
      (node (ref "R13") (pin "1") (pinfunction "1_1") (pintype "passive"))
      (node (ref "U7") (pin "4") (pinfunction "IN-_4") (pintype "input"))
    )
    (net (code "46") (name "Net-(U7-OUT)") (class "Default")
      (node (ref "R14") (pin "2") (pinfunction "2_2") (pintype "passive"))
      (node (ref "U7") (pin "1") (pinfunction "OUT_1") (pintype "output"))
    )
    (net (code "47") (name "Net-(U8-TRIM)") (class "Default")
      (node (ref "R19") (pin "2") (pinfunction "2_2") (pintype "passive"))
      (node (ref "U8") (pin "5") (pinfunction "TRIM_5") (pintype "passive"))
    )
    (net (code "48") (name "Net-(U9--IN)") (class "Default")
      (node (ref "R17") (pin "1") (pinfunction "1_1") (pintype "passive"))
      (node (ref "R18") (pin "2") (pinfunction "2_2") (pintype "passive"))
      (node (ref "U9") (pin "2") (pinfunction "-IN_2") (pintype "input"))
    )
    (net (code "49") (name "Net-(U9-OUT)") (class "Default")
      (node (ref "R18") (pin "1") (pinfunction "1_1") (pintype "passive"))
      (node (ref "R21") (pin "1") (pinfunction "1_1") (pintype "passive"))
      (node (ref "U9") (pin "6") (pinfunction "OUT_6") (pintype "output"))
    )
    (net (code "50") (name "Net-(U10C--IN)") (class "Default")
      (node (ref "R29") (pin "1") (pinfunction "1_1") (pintype "passive"))
      (node (ref "R30") (pin "1") (pinfunction "1_1") (pintype "passive"))
      (node (ref "U10") (pin "9") (pinfunction "-IN_9") (pintype "input"))
    )
    (net (code "51") (name "Net-(U10D-+IN)") (class "Default")
      (node (ref "R24") (pin "2") (pinfunction "2_2") (pintype "passive"))
      (node (ref "R27") (pin "2") (pinfunction "2_2") (pintype "passive"))
      (node (ref "U10") (pin "12") (pinfunction "+IN_12") (pintype "input"))
      (node (ref "U11") (pin "3") (pinfunction "+IN_3") (pintype "input"))
    )
    (net (code "52") (name "Net-(U10D--IN)") (class "Default")
      (node (ref "R22") (pin "1") (pinfunction "1_1") (pintype "passive"))
      (node (ref "R26") (pin "1") (pinfunction "1_1") (pintype "passive"))
      (node (ref "U10") (pin "13") (pinfunction "-IN_13") (pintype "input"))
    )
    (net (code "53") (name "Net-(U11A--IN)") (class "Default")
      (node (ref "C32") (pin "1") (pinfunction "1_1") (pintype "passive"))
      (node (ref "U11") (pin "4") (pinfunction "-IN_4") (pintype "input"))
      (node (ref "U12") (pin "8") (pinfunction "COM_8") (pintype "power_in"))
    )
    (net (code "54") (name "Net-(U11A-OUT)") (class "Default")
      (node (ref "C32") (pin "2") (pinfunction "2_2") (pintype "passive"))
      (node (ref "R28") (pin "1") (pinfunction "1_1") (pintype "passive"))
      (node (ref "U11") (pin "1") (pinfunction "OUT_1") (pintype "output"))
      (node (ref "U13") (pin "2") (pinfunction "B_2") (pintype "input"))
      (node (ref "U13") (pin "5") (pinfunction "B_5") (pintype "input"))
    )
    (net (code "55") (name "Net-(U12-IN)") (class "Default")
      (node (ref "AUX<>CURR") (pin "2") (pinfunction "2_2") (pintype "passive"))
      (node (ref "U12") (pin "3") (pinfunction "IN_3") (pintype "bidirectional"))
    )
    (net (code "56") (name "Net-(U13A-E)") (class "Default")
      (node (ref "R32") (pin "1") (pinfunction "1_1") (pintype "passive"))
      (node (ref "U13") (pin "6") (pinfunction "E_6") (pintype "bidirectional"))
      (node (ref "U14") (pin "5") (pinfunction "B_5") (pintype "input"))
    )
    (net (code "57") (name "Net-(U13B-E)") (class "Default")
      (node (ref "R31") (pin "2") (pinfunction "2_2") (pintype "passive"))
      (node (ref "U13") (pin "4") (pinfunction "E_4") (pintype "bidirectional"))
      (node (ref "U14") (pin "2") (pinfunction "B_2") (pintype "input"))
    )
    (net (code "58") (name "Net-(U14A-E)") (class "Default")
      (node (ref "R33") (pin "1") (pinfunction "1_1") (pintype "passive"))
      (node (ref "U14") (pin "6") (pinfunction "E_6") (pintype "bidirectional"))
    )
    (net (code "59") (name "Net-(U14B-E)") (class "Default")
      (node (ref "R34") (pin "1") (pinfunction "1_1") (pintype "passive"))
      (node (ref "U14") (pin "4") (pinfunction "E_4") (pintype "bidirectional"))
    )
    (net (code "60") (name "OC_COMP") (class "Default")
      (node (ref "LEONARDO") (pin "D2") (pinfunction "D2_D2") (pintype "bidirectional"))
      (node (ref "R16") (pin "2") (pinfunction "2_2") (pintype "passive"))
    )
    (net (code "61") (name "POT") (class "Default")
      (node (ref "LEONARDO") (pin "D12") (pinfunction "D12_D12") (pintype "bidirectional"))
      (node (ref "U3") (pin "3") (pinfunction "U/~{D}_3") (pintype "bidirectional"))
    )
    (net (code "62") (name "POW_IN") (class "Default")
      (node (ref "POWER") (pin "1") (pinfunction "IN_1") (pintype "bidirectional"))
    )
    (net (code "63") (name "REF2.5") (class "Default")
      (node (ref "C4") (pin "1") (pinfunction "1_1") (pintype "passive"))
      (node (ref "REF2.5") (pin "TP") (pinfunction "TP_TP") (pintype "input"))
      (node (ref "REF_ADJ") (pin "1") (pinfunction "A_1") (pintype "passive"))
      (node (ref "U1") (pin "6") (pinfunction "REFA_6") (pintype "input"))
      (node (ref "U8") (pin "4") (pinfunction "VOUT_4") (pintype "output"))
      (node (ref "U9") (pin "3") (pinfunction "+IN_3") (pintype "input"))
    )
    (net (code "64") (name "REF5.0") (class "Default")
      (node (ref "C24") (pin "1") (pinfunction "1_1") (pintype "passive"))
      (node (ref "R21") (pin "2") (pinfunction "2_2") (pintype "passive"))
      (node (ref "REF5.0") (pin "TP") (pinfunction "TP_TP") (pintype "input"))
      (node (ref "TEST") (pin "1") (pinfunction "3_1") (pintype "passive"))
    )
    (net (code "65") (name "SCL") (class "Default")
      (node (ref "EXPANSION") (pin "8") (pinfunction "8_8") (pintype "passive"))
      (node (ref "LEONARDO") (pin "SCL") (pinfunction "SCL_SCL") (pintype "bidirectional"))
      (node (ref "R1") (pin "2") (pinfunction "2_2") (pintype "passive"))
    )
    (net (code "66") (name "SCLK") (class "Default")
      (node (ref "LEONARDO") (pin "SCK") (pinfunction "SCK_SCK") (pintype "passive"))
      (node (ref "U1") (pin "3") (pinfunction "SCK_3") (pintype "input"))
    )
    (net (code "67") (name "SDA") (class "Default")
      (node (ref "EXPANSION") (pin "6") (pinfunction "6_6") (pintype "passive"))
      (node (ref "LEONARDO") (pin "SDA") (pinfunction "SDA_SDA") (pintype "bidirectional"))
      (node (ref "R2") (pin "2") (pinfunction "2_2") (pintype "passive"))
    )
    (net (code "68") (name "SDI") (class "Default")
      (node (ref "LEONARDO") (pin "MOSI") (pinfunction "MOSI_MOSI") (pintype "passive"))
      (node (ref "U1") (pin "4") (pinfunction "SDI_4") (pintype "input"))
    )
    (net (code "69") (name "TRIG") (class "Default")
      (node (ref "T1") (pin "1") (pinfunction "1_1") (pintype "passive"))
      (node (ref "T2") (pin "1") (pinfunction "1_1") (pintype "passive"))
      (node (ref "T3") (pin "1") (pinfunction "1_1") (pintype "passive"))
      (node (ref "T4") (pin "1") (pinfunction "1_1") (pintype "passive"))
      (node (ref "U2") (pin "2") (pinfunction "A_2") (pintype "bidirectional"))
    )
    (net (code "70") (name "TRIG_EXT") (class "Default")
      (node (ref "TRIG") (pin "1") (pinfunction "1_1") (pintype "passive"))
      (node (ref "U2") (pin "5") (pinfunction "Y_5") (pintype "bidirectional"))
    )
    (net (code "71") (name "VAUX") (class "Default")
      (node (ref "EXPANSION") (pin "9") (pinfunction "9_9") (pintype "passive"))
      (node (ref "R25") (pin "1") (pinfunction "1_1") (pintype "passive"))
      (node (ref "U10") (pin "5") (pinfunction "+IN_5") (pintype "input"))
      (node (ref "U12") (pin "4") (pinfunction "NO_4") (pintype "bidirectional"))
      (node (ref "VAUX_IN") (pin "1") (pinfunction "1_1") (pintype "passive"))
    )
    (net (code "72") (name "VAUX_OUT") (class "Default")
      (node (ref "U10") (pin "6") (pinfunction "-IN_6") (pintype "input"))
      (node (ref "U10") (pin "7") (pinfunction "OUT_7") (pintype "output"))
      (node (ref "VAUX_OUT") (pin "1") (pinfunction "1_1") (pintype "passive"))
    )
    (net (code "73") (name "VCTL") (class "Default")
      (node (ref "D1") (pin "C") (pinfunction "C_C") (pintype "passive"))
      (node (ref "R23") (pin "2") (pinfunction "2_2") (pintype "passive"))
      (node (ref "R5") (pin "2") (pinfunction "2_2") (pintype "passive"))
      (node (ref "U3") (pin "6") (pinfunction "A_6") (pintype "bidirectional"))
      (node (ref "VPRE") (pin "TP") (pinfunction "TP_TP") (pintype "input"))
    )
    (net (code "74") (name "VCTL_PROTECT") (class "Default")
      (node (ref "GAIN") (pin "3") (pinfunction "A_3") (pintype "passive"))
      (node (ref "R23") (pin "1") (pinfunction "1_1") (pintype "passive"))
      (node (ref "U3") (pin "5") (pinfunction "W_5") (pintype "bidirectional"))
    )
    (net (code "75") (name "VI") (class "Default")
      (node (ref "R11") (pin "2") (pinfunction "2_2") (pintype "passive"))
      (node (ref "R29") (pin "2") (pinfunction "2_2") (pintype "passive"))
      (node (ref "R3") (pin "1") (pinfunction "1_1") (pintype "passive"))
      (node (ref "U10") (pin "8") (pinfunction "OUT_8") (pintype "output"))
      (node (ref "VI") (pin "1") (pinfunction "1_1") (pintype "passive"))
    )
    (net (code "76") (name "VINPUT") (class "Default")
      (node (ref "VCTL") (pin "1") (pinfunction "1_1") (pintype "passive"))
      (node (ref "VCTL<OFF>DAC") (pin "3") (pinfunction "3_3") (pintype "passive"))
    )
    (net (code "77") (name "VIN_ARDUINO") (class "Default")
      (node (ref "L2") (pin "1") (pinfunction "1_1") (pintype "passive"))
      (node (ref "LEONARDO") (pin "VIN") (pinfunction "VIN_VIN") (pintype "power_in"))
      (node (ref "NEG_SUPPLY") (pin "3") (pinfunction "3_3") (pintype "passive"))
    )
    (net (code "78") (name "VLOGIC") (class "Default")
      (node (ref "C7") (pin "1") (pinfunction "1_1") (pintype "passive"))
      (node (ref "LEONARDO") (pin "IOREF") (pinfunction "IOREF_IOREF") (pintype "output"))
      (node (ref "U2") (pin "1") (pinfunction "VCCA_1") (pintype "power_in"))
      (node (ref "U2") (pin "4") (pinfunction "EN_4") (pintype "input"))
    )
    (net (code "79") (name "VREF") (class "Default")
      (node (ref "R22") (pin "2") (pinfunction "2_2") (pintype "passive"))
      (node (ref "U10") (pin "14") (pinfunction "OUT_14") (pintype "output"))
      (node (ref "VREF") (pin "1") (pinfunction "1_1") (pintype "passive"))
    )
    (net (code "80") (name "unconnected-(LEONARDO-NC-PadRESERVED)") (class "Default")
      (node (ref "LEONARDO") (pin "RESERVED") (pinfunction "NC_RESERVED") (pintype "no_connect"))
    )
    (net (code "81") (name "unconnected-(LEONARDO-Pad3V)") (class "Default")
      (node (ref "LEONARDO") (pin "3V") (pinfunction "3V_3V") (pintype "passive"))
    )
    (net (code "82") (name "unconnected-(LEONARDO-PadA4)") (class "Default")
      (node (ref "LEONARDO") (pin "A4") (pinfunction "A4_A4") (pintype "bidirectional"))
    )
    (net (code "83") (name "unconnected-(LEONARDO-PadA5)") (class "Default")
      (node (ref "LEONARDO") (pin "A5") (pinfunction "A5_A5") (pintype "bidirectional"))
    )
    (net (code "84") (name "unconnected-(LEONARDO-PadAREF)") (class "Default")
      (node (ref "LEONARDO") (pin "AREF") (pinfunction "AREF_AREF") (pintype "bidirectional"))
    )
    (net (code "85") (name "unconnected-(LEONARDO-PadD0)") (class "Default")
      (node (ref "LEONARDO") (pin "D0") (pinfunction "D0_D0") (pintype "bidirectional"))
    )
    (net (code "86") (name "unconnected-(LEONARDO-PadD1)") (class "Default")
      (node (ref "LEONARDO") (pin "D1") (pinfunction "D1_D1") (pintype "bidirectional"))
    )
    (net (code "87") (name "unconnected-(LEONARDO-PadD13)") (class "Default")
      (node (ref "LEONARDO") (pin "D13") (pinfunction "D13_D13") (pintype "bidirectional"))
    )
    (net (code "88") (name "unconnected-(LEONARDO-PadGND)") (class "Default")
      (node (ref "LEONARDO") (pin "GND") (pinfunction "GND_GND") (pintype "passive"))
    )
    (net (code "89") (name "unconnected-(LEONARDO-PadGND3)") (class "Default")
      (node (ref "LEONARDO") (pin "GND3") (pinfunction "GND3_GND3") (pintype "passive"))
    )
    (net (code "90") (name "unconnected-(LEONARDO-PadMISO)") (class "Default")
      (node (ref "LEONARDO") (pin "MISO") (pinfunction "MISO_MISO") (pintype "passive"))
    )
    (net (code "91") (name "unconnected-(LEONARDO-RST-PadRESET)") (class "Default")
      (node (ref "LEONARDO") (pin "RESET") (pinfunction "RST_RESET") (pintype "passive"))
    )
    (net (code "92") (name "unconnected-(LEONARDO-{slash}RESET-PadRESET$1)") (class "Default")
      (node (ref "LEONARDO") (pin "RESET$1") (pinfunction "/RESET_RESET$1") (pintype "bidirectional"))
    )
    (net (code "93") (name "unconnected-(U8-TEMP-Pad1)") (class "Default")
      (node (ref "U8") (pin "1") (pinfunction "TEMP_1") (pintype "passive"))
    )
    (net (code "94") (name "unconnected-(U9-NC-Pad1)") (class "Default")
      (node (ref "U9") (pin "1") (pinfunction "NC_1") (pintype "no_connect"))
    )
    (net (code "95") (name "unconnected-(U9-NC_2-Pad5)") (class "Default")
      (node (ref "U9") (pin "5") (pinfunction "NC_2_5") (pintype "no_connect"))
    )
    (net (code "96") (name "unconnected-(U9-NC_3-Pad8)") (class "Default")
      (node (ref "U9") (pin "8") (pinfunction "NC_3_8") (pintype "no_connect"))
    )
  )
)
